# tester.net
KiCad netlist of a schematic drawn in EAGLE
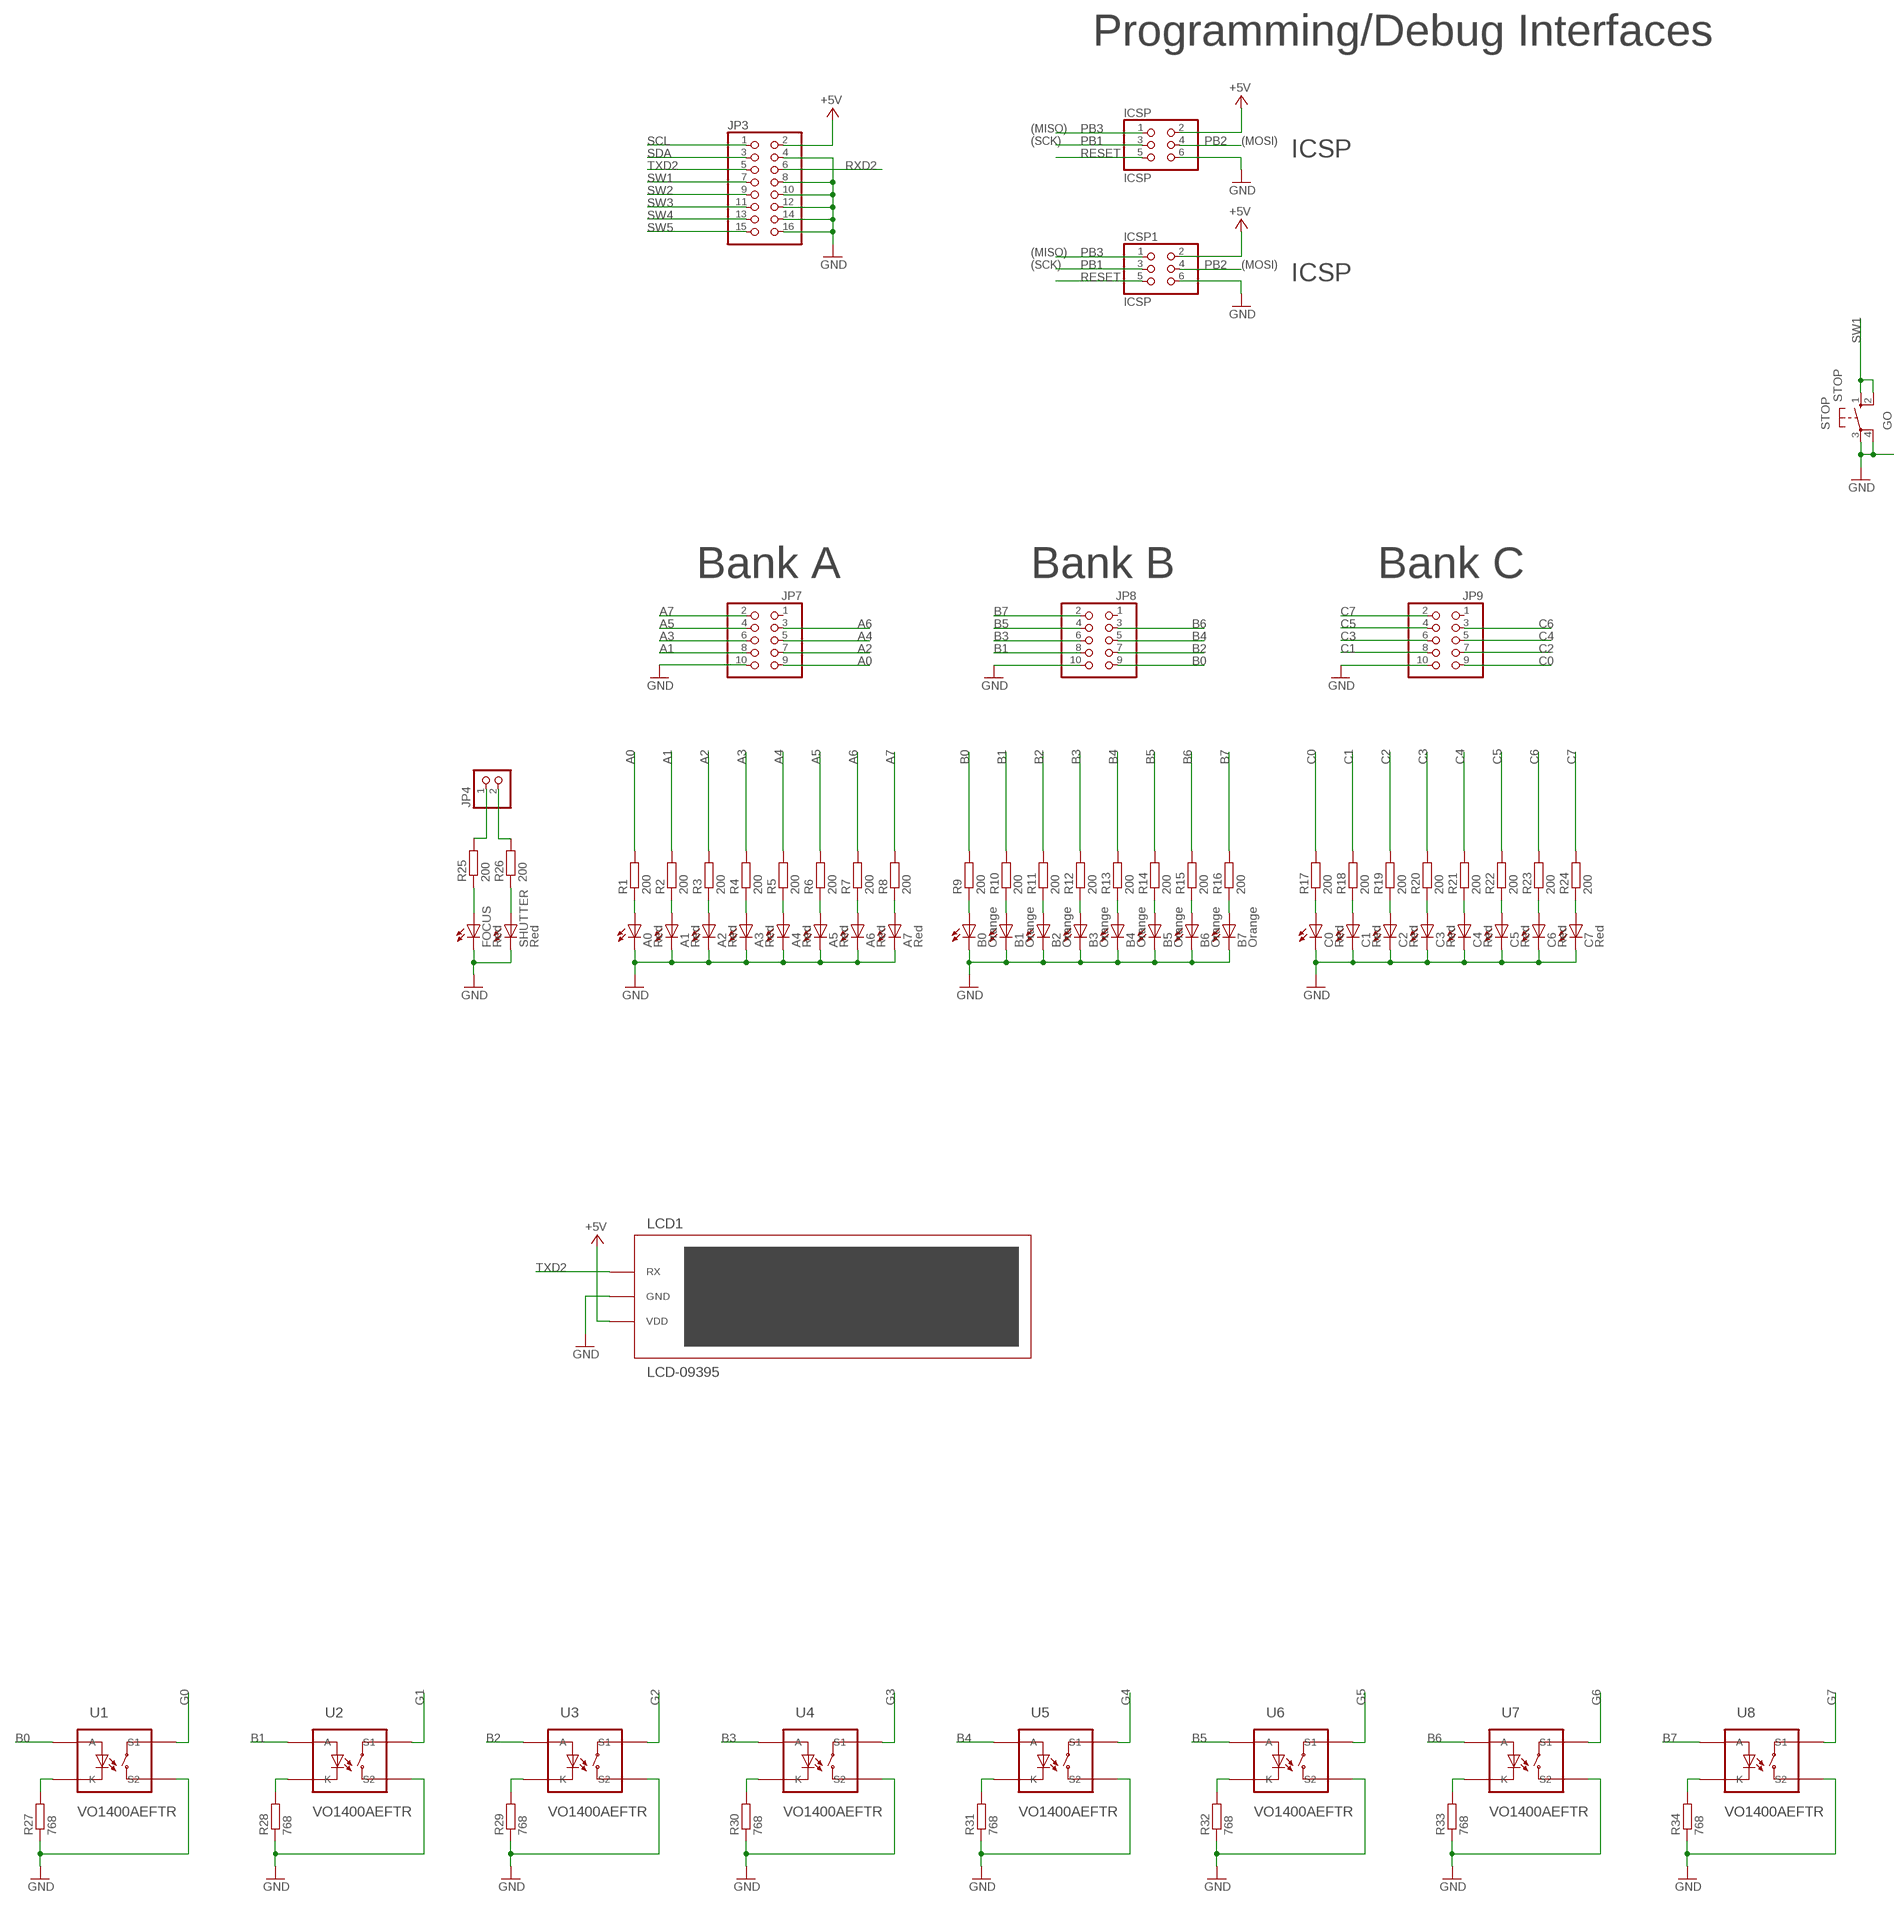
[diagram p0: schematic, sheet 1, part 1 of 2]
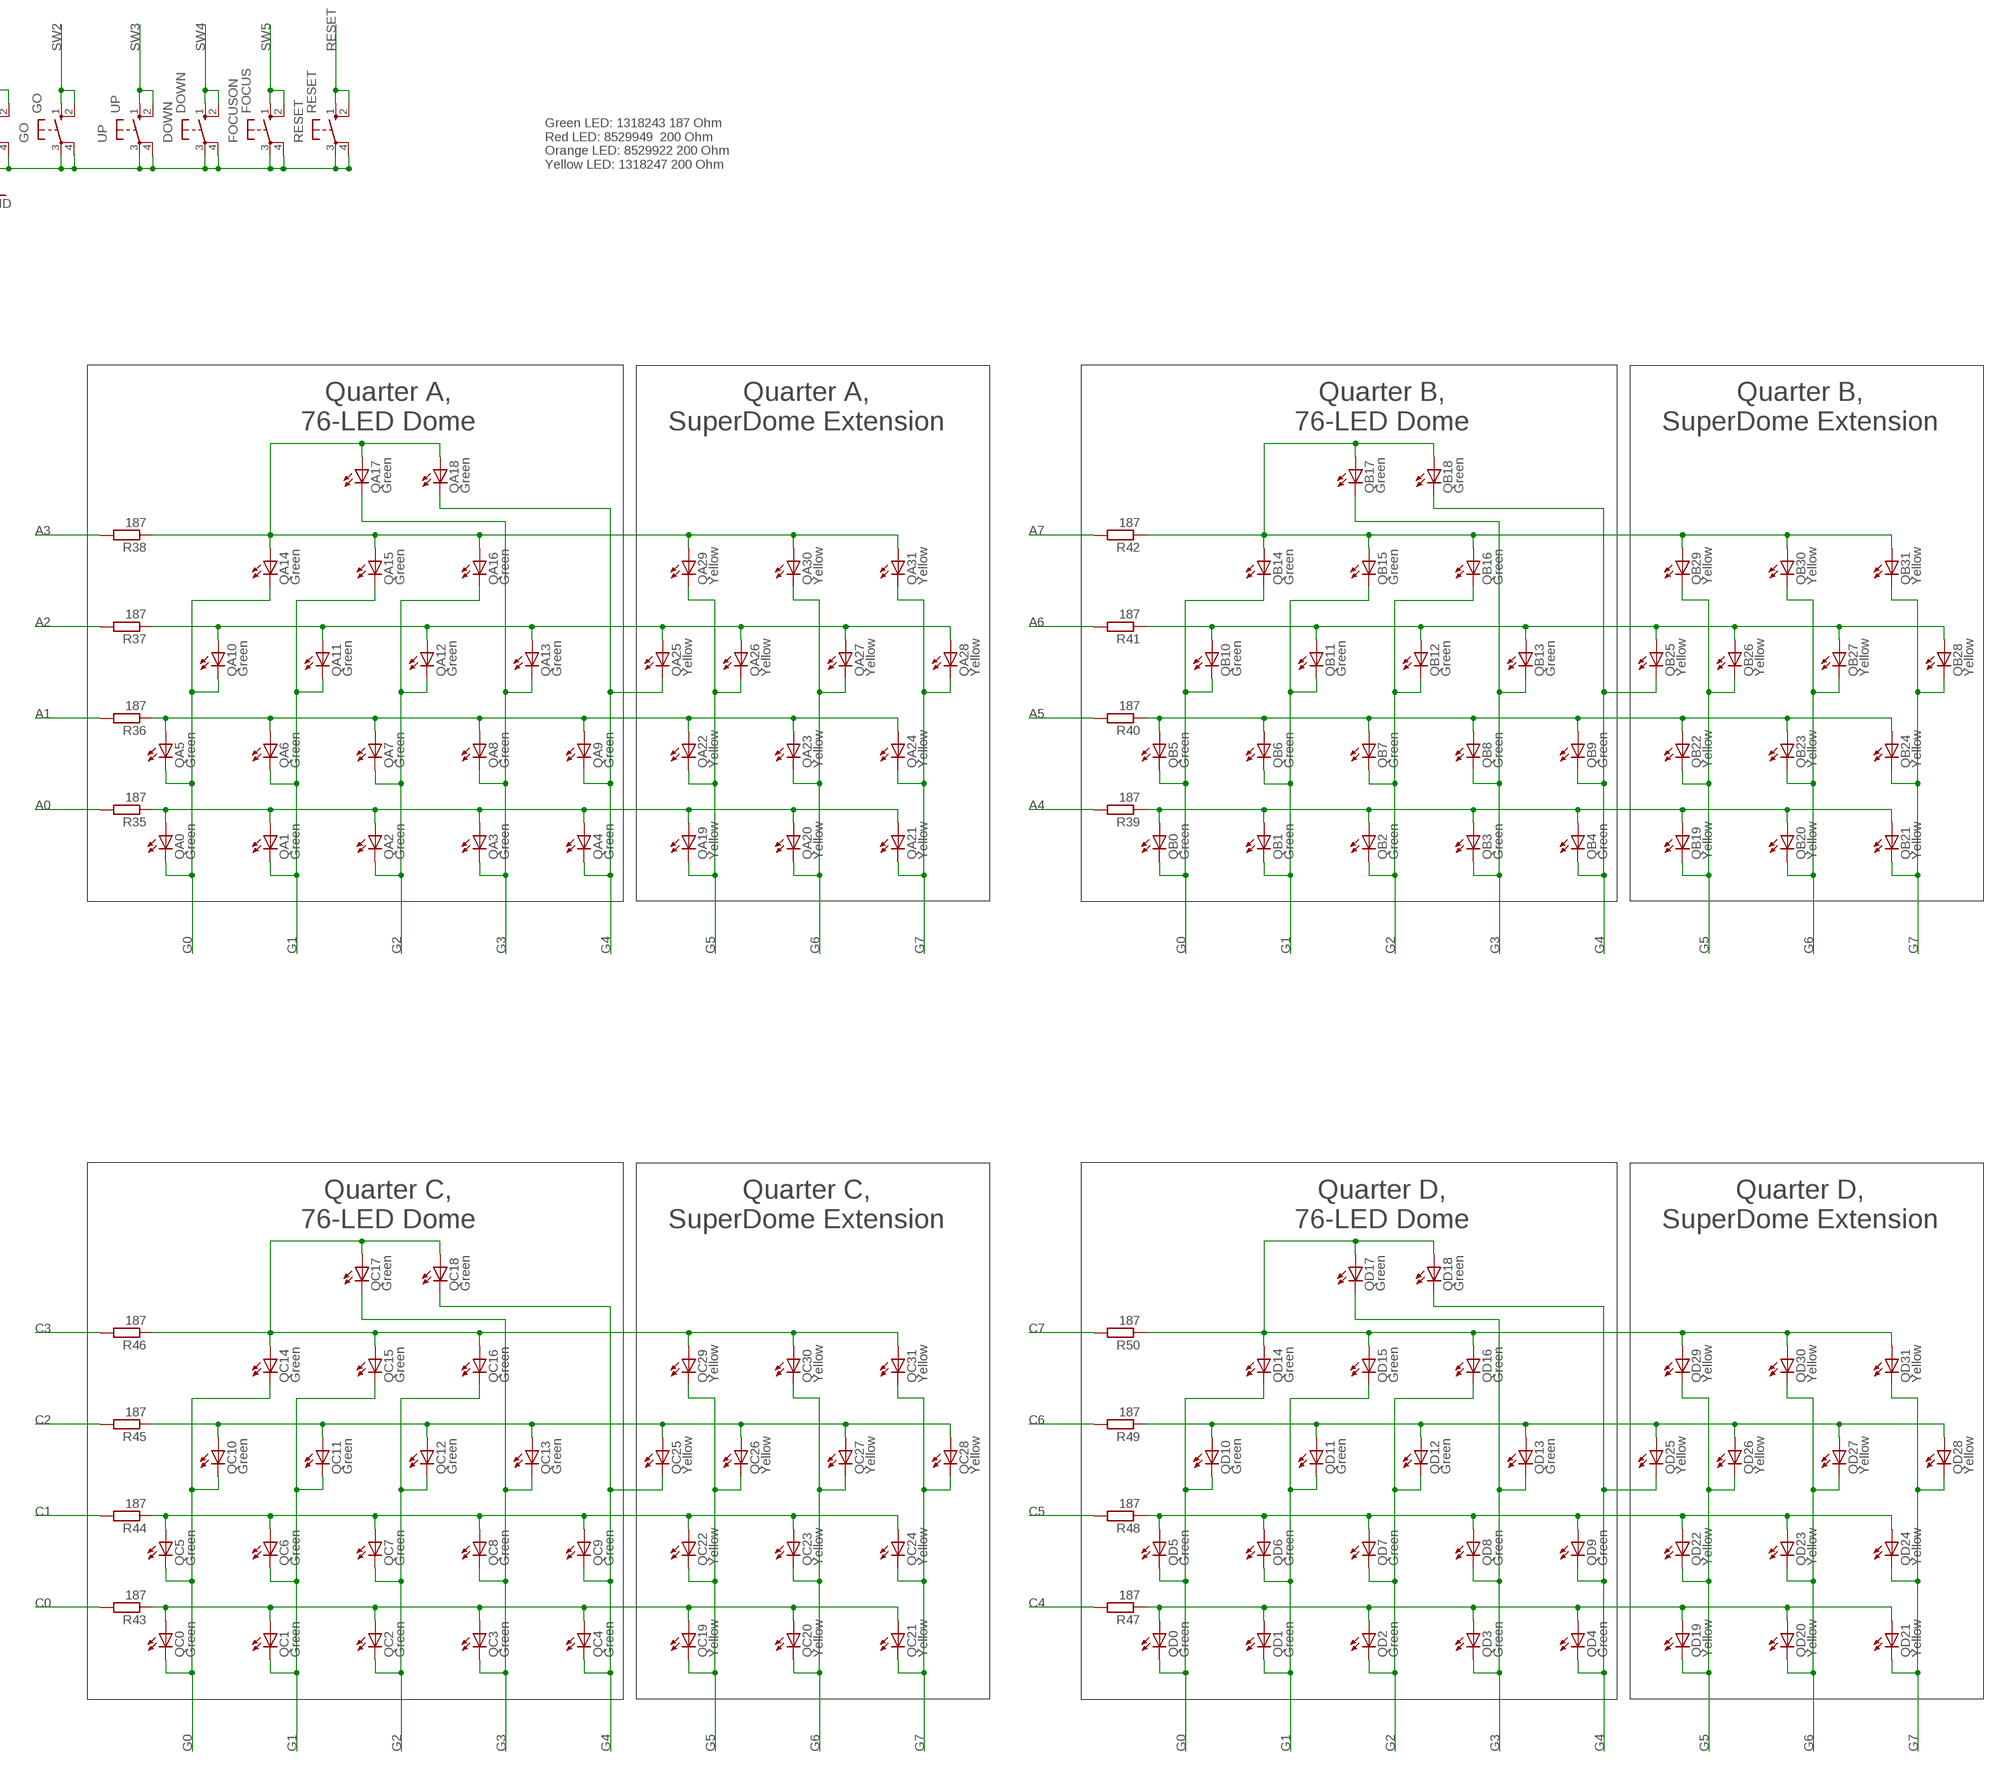
[diagram p1: schematic, sheet 1, part 2 of 2]

(export (version "E")
  (design (tool "Eeschema 10.0.6"))
  (components
    (comp (ref "A0")
      (value "Red")
      (footprint "eagle-import:CHIP-LED0805")
      (libsource (lib "eagle-import") (part "LEDCHIP-LED0805"))
    )
    (comp (ref "A1")
      (value "Red")
      (footprint "eagle-import:CHIP-LED0805")
      (libsource (lib "eagle-import") (part "LEDCHIP-LED0805"))
    )
    (comp (ref "A2")
      (value "Red")
      (footprint "eagle-import:CHIP-LED0805")
      (libsource (lib "eagle-import") (part "LEDCHIP-LED0805"))
    )
    (comp (ref "A3")
      (value "Red")
      (footprint "eagle-import:CHIP-LED0805")
      (libsource (lib "eagle-import") (part "LEDCHIP-LED0805"))
    )
    (comp (ref "A4")
      (value "Red")
      (footprint "eagle-import:CHIP-LED0805")
      (libsource (lib "eagle-import") (part "LEDCHIP-LED0805"))
    )
    (comp (ref "A5")
      (value "Red")
      (footprint "eagle-import:CHIP-LED0805")
      (libsource (lib "eagle-import") (part "LEDCHIP-LED0805"))
    )
    (comp (ref "A6")
      (value "Red")
      (footprint "eagle-import:CHIP-LED0805")
      (libsource (lib "eagle-import") (part "LEDCHIP-LED0805"))
    )
    (comp (ref "A7")
      (value "Red")
      (footprint "eagle-import:CHIP-LED0805")
      (libsource (lib "eagle-import") (part "LEDCHIP-LED0805"))
    )
    (comp (ref "B0")
      (value "Orange")
      (footprint "eagle-import:CHIP-LED0805")
      (libsource (lib "eagle-import") (part "LEDCHIP-LED0805"))
    )
    (comp (ref "B1")
      (value "Orange")
      (footprint "eagle-import:CHIP-LED0805")
      (libsource (lib "eagle-import") (part "LEDCHIP-LED0805"))
    )
    (comp (ref "B2")
      (value "Orange")
      (footprint "eagle-import:CHIP-LED0805")
      (libsource (lib "eagle-import") (part "LEDCHIP-LED0805"))
    )
    (comp (ref "B3")
      (value "Orange")
      (footprint "eagle-import:CHIP-LED0805")
      (libsource (lib "eagle-import") (part "LEDCHIP-LED0805"))
    )
    (comp (ref "B4")
      (value "Orange")
      (footprint "eagle-import:CHIP-LED0805")
      (libsource (lib "eagle-import") (part "LEDCHIP-LED0805"))
    )
    (comp (ref "B5")
      (value "Orange")
      (footprint "eagle-import:CHIP-LED0805")
      (libsource (lib "eagle-import") (part "LEDCHIP-LED0805"))
    )
    (comp (ref "B6")
      (value "Orange")
      (footprint "eagle-import:CHIP-LED0805")
      (libsource (lib "eagle-import") (part "LEDCHIP-LED0805"))
    )
    (comp (ref "B7")
      (value "Orange")
      (footprint "eagle-import:CHIP-LED0805")
      (libsource (lib "eagle-import") (part "LEDCHIP-LED0805"))
    )
    (comp (ref "C0")
      (value "Red")
      (footprint "eagle-import:CHIP-LED0805")
      (libsource (lib "eagle-import") (part "LEDCHIP-LED0805"))
    )
    (comp (ref "C1")
      (value "Red")
      (footprint "eagle-import:CHIP-LED0805")
      (libsource (lib "eagle-import") (part "LEDCHIP-LED0805"))
    )
    (comp (ref "C2")
      (value "Red")
      (footprint "eagle-import:CHIP-LED0805")
      (libsource (lib "eagle-import") (part "LEDCHIP-LED0805"))
    )
    (comp (ref "C3")
      (value "Red")
      (footprint "eagle-import:CHIP-LED0805")
      (libsource (lib "eagle-import") (part "LEDCHIP-LED0805"))
    )
    (comp (ref "C4")
      (value "Red")
      (footprint "eagle-import:CHIP-LED0805")
      (libsource (lib "eagle-import") (part "LEDCHIP-LED0805"))
    )
    (comp (ref "C5")
      (value "Red")
      (footprint "eagle-import:CHIP-LED0805")
      (libsource (lib "eagle-import") (part "LEDCHIP-LED0805"))
    )
    (comp (ref "C6")
      (value "Red")
      (footprint "eagle-import:CHIP-LED0805")
      (libsource (lib "eagle-import") (part "LEDCHIP-LED0805"))
    )
    (comp (ref "C7")
      (value "Red")
      (footprint "eagle-import:CHIP-LED0805")
      (libsource (lib "eagle-import") (part "LEDCHIP-LED0805"))
    )
    (comp (ref "DOWN")
      (value "DOWN")
      (footprint "eagle-import:B3F-10XX")
      (fields (field (name "MPN") "B3F-1000"))
      (libsource (lib "eagle-import") (part "10-XX"))
    )
    (comp (ref "FOCUS")
      (value "Red")
      (footprint "eagle-import:CHIP-LED0805")
      (libsource (lib "eagle-import") (part "LEDCHIP-LED0805"))
    )
    (comp (ref "FOCUSON")
      (value "FOCUS")
      (footprint "eagle-import:B3F-10XX")
      (fields (field (name "MPN") "B3F-1000"))
      (libsource (lib "eagle-import") (part "10-XX"))
    )
    (comp (ref "GO")
      (value "GO")
      (footprint "eagle-import:B3F-10XX")
      (fields (field (name "MPN") "B3F-1000"))
      (libsource (lib "eagle-import") (part "10-XX"))
    )
    (comp (ref "ICSP")
      (value "ICSP")
      (footprint "eagle-import:2X03")
      (libsource (lib "eagle-import") (part "PINHD-2X3"))
    )
    (comp (ref "ICSP1")
      (value "ICSP")
      (footprint "eagle-import:2X03")
      (libsource (lib "eagle-import") (part "PINHD-2X3"))
    )
    (comp (ref "JP3")
      (value "PINHD-2X8")
      (footprint "eagle-import:2X08")
      (libsource (lib "eagle-import") (part "PINHD-2X8"))
    )
    (comp (ref "JP4")
      (value "PINHD-1X2")
      (footprint "eagle-import:1X02")
      (libsource (lib "eagle-import") (part "PINHD-1X2"))
    )
    (comp (ref "JP7")
      (value "PINHD-2X5")
      (footprint "eagle-import:2X05")
      (libsource (lib "eagle-import") (part "PINHD-2X5"))
    )
    (comp (ref "JP8")
      (value "PINHD-2X5")
      (footprint "eagle-import:2X05")
      (libsource (lib "eagle-import") (part "PINHD-2X5"))
    )
    (comp (ref "JP9")
      (value "PINHD-2X5")
      (footprint "eagle-import:2X05")
      (libsource (lib "eagle-import") (part "PINHD-2X5"))
    )
    (comp (ref "LCD1")
      (value "LCD-09395")
      (footprint "eagle-import:LCD-09395")
      (libsource (lib "eagle-import") (part "LCD-09395"))
    )
    (comp (ref "QA0")
      (value "Green")
      (footprint "eagle-import:CHIP-LED0805")
      (libsource (lib "eagle-import") (part "LEDCHIP-LED0805"))
    )
    (comp (ref "QA1")
      (value "Green")
      (footprint "eagle-import:CHIP-LED0805")
      (libsource (lib "eagle-import") (part "LEDCHIP-LED0805"))
    )
    (comp (ref "QA2")
      (value "Green")
      (footprint "eagle-import:CHIP-LED0805")
      (libsource (lib "eagle-import") (part "LEDCHIP-LED0805"))
    )
    (comp (ref "QA3")
      (value "Green")
      (footprint "eagle-import:CHIP-LED0805")
      (libsource (lib "eagle-import") (part "LEDCHIP-LED0805"))
    )
    (comp (ref "QA4")
      (value "Green")
      (footprint "eagle-import:CHIP-LED0805")
      (libsource (lib "eagle-import") (part "LEDCHIP-LED0805"))
    )
    (comp (ref "QA5")
      (value "Green")
      (footprint "eagle-import:CHIP-LED0805")
      (libsource (lib "eagle-import") (part "LEDCHIP-LED0805"))
    )
    (comp (ref "QA6")
      (value "Green")
      (footprint "eagle-import:CHIP-LED0805")
      (libsource (lib "eagle-import") (part "LEDCHIP-LED0805"))
    )
    (comp (ref "QA7")
      (value "Green")
      (footprint "eagle-import:CHIP-LED0805")
      (libsource (lib "eagle-import") (part "LEDCHIP-LED0805"))
    )
    (comp (ref "QA8")
      (value "Green")
      (footprint "eagle-import:CHIP-LED0805")
      (libsource (lib "eagle-import") (part "LEDCHIP-LED0805"))
    )
    (comp (ref "QA9")
      (value "Green")
      (footprint "eagle-import:CHIP-LED0805")
      (libsource (lib "eagle-import") (part "LEDCHIP-LED0805"))
    )
    (comp (ref "QA10")
      (value "Green")
      (footprint "eagle-import:CHIP-LED0805")
      (libsource (lib "eagle-import") (part "LEDCHIP-LED0805"))
    )
    (comp (ref "QA11")
      (value "Green")
      (footprint "eagle-import:CHIP-LED0805")
      (libsource (lib "eagle-import") (part "LEDCHIP-LED0805"))
    )
    (comp (ref "QA12")
      (value "Green")
      (footprint "eagle-import:CHIP-LED0805")
      (libsource (lib "eagle-import") (part "LEDCHIP-LED0805"))
    )
    (comp (ref "QA13")
      (value "Green")
      (footprint "eagle-import:CHIP-LED0805")
      (libsource (lib "eagle-import") (part "LEDCHIP-LED0805"))
    )
    (comp (ref "QA14")
      (value "Green")
      (footprint "eagle-import:CHIP-LED0805")
      (libsource (lib "eagle-import") (part "LEDCHIP-LED0805"))
    )
    (comp (ref "QA15")
      (value "Green")
      (footprint "eagle-import:CHIP-LED0805")
      (libsource (lib "eagle-import") (part "LEDCHIP-LED0805"))
    )
    (comp (ref "QA16")
      (value "Green")
      (footprint "eagle-import:CHIP-LED0805")
      (libsource (lib "eagle-import") (part "LEDCHIP-LED0805"))
    )
    (comp (ref "QA17")
      (value "Green")
      (footprint "eagle-import:CHIP-LED0805")
      (libsource (lib "eagle-import") (part "LEDCHIP-LED0805"))
    )
    (comp (ref "QA18")
      (value "Green")
      (footprint "eagle-import:CHIP-LED0805")
      (libsource (lib "eagle-import") (part "LEDCHIP-LED0805"))
    )
    (comp (ref "QA19")
      (value "Yellow")
      (footprint "eagle-import:CHIP-LED0805")
      (libsource (lib "eagle-import") (part "LEDCHIP-LED0805"))
    )
    (comp (ref "QA20")
      (value "Yellow")
      (footprint "eagle-import:CHIP-LED0805")
      (libsource (lib "eagle-import") (part "LEDCHIP-LED0805"))
    )
    (comp (ref "QA21")
      (value "Yellow")
      (footprint "eagle-import:CHIP-LED0805")
      (libsource (lib "eagle-import") (part "LEDCHIP-LED0805"))
    )
    (comp (ref "QA22")
      (value "Yellow")
      (footprint "eagle-import:CHIP-LED0805")
      (libsource (lib "eagle-import") (part "LEDCHIP-LED0805"))
    )
    (comp (ref "QA23")
      (value "Yellow")
      (footprint "eagle-import:CHIP-LED0805")
      (libsource (lib "eagle-import") (part "LEDCHIP-LED0805"))
    )
    (comp (ref "QA24")
      (value "Yellow")
      (footprint "eagle-import:CHIP-LED0805")
      (libsource (lib "eagle-import") (part "LEDCHIP-LED0805"))
    )
    (comp (ref "QA25")
      (value "Yellow")
      (footprint "eagle-import:CHIP-LED0805")
      (libsource (lib "eagle-import") (part "LEDCHIP-LED0805"))
    )
    (comp (ref "QA26")
      (value "Yellow")
      (footprint "eagle-import:CHIP-LED0805")
      (libsource (lib "eagle-import") (part "LEDCHIP-LED0805"))
    )
    (comp (ref "QA27")
      (value "Yellow")
      (footprint "eagle-import:CHIP-LED0805")
      (libsource (lib "eagle-import") (part "LEDCHIP-LED0805"))
    )
    (comp (ref "QA28")
      (value "Yellow")
      (footprint "eagle-import:CHIP-LED0805")
      (libsource (lib "eagle-import") (part "LEDCHIP-LED0805"))
    )
    (comp (ref "QA29")
      (value "Yellow")
      (footprint "eagle-import:CHIP-LED0805")
      (libsource (lib "eagle-import") (part "LEDCHIP-LED0805"))
    )
    (comp (ref "QA30")
      (value "Yellow")
      (footprint "eagle-import:CHIP-LED0805")
      (libsource (lib "eagle-import") (part "LEDCHIP-LED0805"))
    )
    (comp (ref "QA31")
      (value "Yellow")
      (footprint "eagle-import:CHIP-LED0805")
      (libsource (lib "eagle-import") (part "LEDCHIP-LED0805"))
    )
    (comp (ref "QB0")
      (value "Green")
      (footprint "eagle-import:CHIP-LED0805")
      (libsource (lib "eagle-import") (part "LEDCHIP-LED0805"))
    )
    (comp (ref "QB1")
      (value "Green")
      (footprint "eagle-import:CHIP-LED0805")
      (libsource (lib "eagle-import") (part "LEDCHIP-LED0805"))
    )
    (comp (ref "QB2")
      (value "Green")
      (footprint "eagle-import:CHIP-LED0805")
      (libsource (lib "eagle-import") (part "LEDCHIP-LED0805"))
    )
    (comp (ref "QB3")
      (value "Green")
      (footprint "eagle-import:CHIP-LED0805")
      (libsource (lib "eagle-import") (part "LEDCHIP-LED0805"))
    )
    (comp (ref "QB4")
      (value "Green")
      (footprint "eagle-import:CHIP-LED0805")
      (libsource (lib "eagle-import") (part "LEDCHIP-LED0805"))
    )
    (comp (ref "QB5")
      (value "Green")
      (footprint "eagle-import:CHIP-LED0805")
      (libsource (lib "eagle-import") (part "LEDCHIP-LED0805"))
    )
    (comp (ref "QB6")
      (value "Green")
      (footprint "eagle-import:CHIP-LED0805")
      (libsource (lib "eagle-import") (part "LEDCHIP-LED0805"))
    )
    (comp (ref "QB7")
      (value "Green")
      (footprint "eagle-import:CHIP-LED0805")
      (libsource (lib "eagle-import") (part "LEDCHIP-LED0805"))
    )
    (comp (ref "QB8")
      (value "Green")
      (footprint "eagle-import:CHIP-LED0805")
      (libsource (lib "eagle-import") (part "LEDCHIP-LED0805"))
    )
    (comp (ref "QB9")
      (value "Green")
      (footprint "eagle-import:CHIP-LED0805")
      (libsource (lib "eagle-import") (part "LEDCHIP-LED0805"))
    )
    (comp (ref "QB10")
      (value "Green")
      (footprint "eagle-import:CHIP-LED0805")
      (libsource (lib "eagle-import") (part "LEDCHIP-LED0805"))
    )
    (comp (ref "QB11")
      (value "Green")
      (footprint "eagle-import:CHIP-LED0805")
      (libsource (lib "eagle-import") (part "LEDCHIP-LED0805"))
    )
    (comp (ref "QB12")
      (value "Green")
      (footprint "eagle-import:CHIP-LED0805")
      (libsource (lib "eagle-import") (part "LEDCHIP-LED0805"))
    )
    (comp (ref "QB13")
      (value "Green")
      (footprint "eagle-import:CHIP-LED0805")
      (libsource (lib "eagle-import") (part "LEDCHIP-LED0805"))
    )
    (comp (ref "QB14")
      (value "Green")
      (footprint "eagle-import:CHIP-LED0805")
      (libsource (lib "eagle-import") (part "LEDCHIP-LED0805"))
    )
    (comp (ref "QB15")
      (value "Green")
      (footprint "eagle-import:CHIP-LED0805")
      (libsource (lib "eagle-import") (part "LEDCHIP-LED0805"))
    )
    (comp (ref "QB16")
      (value "Green")
      (footprint "eagle-import:CHIP-LED0805")
      (libsource (lib "eagle-import") (part "LEDCHIP-LED0805"))
    )
    (comp (ref "QB17")
      (value "Green")
      (footprint "eagle-import:CHIP-LED0805")
      (libsource (lib "eagle-import") (part "LEDCHIP-LED0805"))
    )
    (comp (ref "QB18")
      (value "Green")
      (footprint "eagle-import:CHIP-LED0805")
      (libsource (lib "eagle-import") (part "LEDCHIP-LED0805"))
    )
    (comp (ref "QB19")
      (value "Yellow")
      (footprint "eagle-import:CHIP-LED0805")
      (libsource (lib "eagle-import") (part "LEDCHIP-LED0805"))
    )
    (comp (ref "QB20")
      (value "Yellow")
      (footprint "eagle-import:CHIP-LED0805")
      (libsource (lib "eagle-import") (part "LEDCHIP-LED0805"))
    )
    (comp (ref "QB21")
      (value "Yellow")
      (footprint "eagle-import:CHIP-LED0805")
      (libsource (lib "eagle-import") (part "LEDCHIP-LED0805"))
    )
    (comp (ref "QB22")
      (value "Yellow")
      (footprint "eagle-import:CHIP-LED0805")
      (libsource (lib "eagle-import") (part "LEDCHIP-LED0805"))
    )
    (comp (ref "QB23")
      (value "Yellow")
      (footprint "eagle-import:CHIP-LED0805")
      (libsource (lib "eagle-import") (part "LEDCHIP-LED0805"))
    )
    (comp (ref "QB24")
      (value "Yellow")
      (footprint "eagle-import:CHIP-LED0805")
      (libsource (lib "eagle-import") (part "LEDCHIP-LED0805"))
    )
    (comp (ref "QB25")
      (value "Yellow")
      (footprint "eagle-import:CHIP-LED0805")
      (libsource (lib "eagle-import") (part "LEDCHIP-LED0805"))
    )
    (comp (ref "QB26")
      (value "Yellow")
      (footprint "eagle-import:CHIP-LED0805")
      (libsource (lib "eagle-import") (part "LEDCHIP-LED0805"))
    )
    (comp (ref "QB27")
      (value "Yellow")
      (footprint "eagle-import:CHIP-LED0805")
      (libsource (lib "eagle-import") (part "LEDCHIP-LED0805"))
    )
    (comp (ref "QB28")
      (value "Yellow")
      (footprint "eagle-import:CHIP-LED0805")
      (libsource (lib "eagle-import") (part "LEDCHIP-LED0805"))
    )
    (comp (ref "QB29")
      (value "Yellow")
      (footprint "eagle-import:CHIP-LED0805")
      (libsource (lib "eagle-import") (part "LEDCHIP-LED0805"))
    )
    (comp (ref "QB30")
      (value "Yellow")
      (footprint "eagle-import:CHIP-LED0805")
      (libsource (lib "eagle-import") (part "LEDCHIP-LED0805"))
    )
    (comp (ref "QB31")
      (value "Yellow")
      (footprint "eagle-import:CHIP-LED0805")
      (libsource (lib "eagle-import") (part "LEDCHIP-LED0805"))
    )
    (comp (ref "QC0")
      (value "Green")
      (footprint "eagle-import:CHIP-LED0805")
      (libsource (lib "eagle-import") (part "LEDCHIP-LED0805"))
    )
    (comp (ref "QC1")
      (value "Green")
      (footprint "eagle-import:CHIP-LED0805")
      (libsource (lib "eagle-import") (part "LEDCHIP-LED0805"))
    )
    (comp (ref "QC2")
      (value "Green")
      (footprint "eagle-import:CHIP-LED0805")
      (libsource (lib "eagle-import") (part "LEDCHIP-LED0805"))
    )
    (comp (ref "QC3")
      (value "Green")
      (footprint "eagle-import:CHIP-LED0805")
      (libsource (lib "eagle-import") (part "LEDCHIP-LED0805"))
    )
    (comp (ref "QC4")
      (value "Green")
      (footprint "eagle-import:CHIP-LED0805")
      (libsource (lib "eagle-import") (part "LEDCHIP-LED0805"))
    )
    (comp (ref "QC5")
      (value "Green")
      (footprint "eagle-import:CHIP-LED0805")
      (libsource (lib "eagle-import") (part "LEDCHIP-LED0805"))
    )
    (comp (ref "QC6")
      (value "Green")
      (footprint "eagle-import:CHIP-LED0805")
      (libsource (lib "eagle-import") (part "LEDCHIP-LED0805"))
    )
    (comp (ref "QC7")
      (value "Green")
      (footprint "eagle-import:CHIP-LED0805")
      (libsource (lib "eagle-import") (part "LEDCHIP-LED0805"))
    )
    (comp (ref "QC8")
      (value "Green")
      (footprint "eagle-import:CHIP-LED0805")
      (libsource (lib "eagle-import") (part "LEDCHIP-LED0805"))
    )
    (comp (ref "QC9")
      (value "Green")
      (footprint "eagle-import:CHIP-LED0805")
      (libsource (lib "eagle-import") (part "LEDCHIP-LED0805"))
    )
    (comp (ref "QC10")
      (value "Green")
      (footprint "eagle-import:CHIP-LED0805")
      (libsource (lib "eagle-import") (part "LEDCHIP-LED0805"))
    )
    (comp (ref "QC11")
      (value "Green")
      (footprint "eagle-import:CHIP-LED0805")
      (libsource (lib "eagle-import") (part "LEDCHIP-LED0805"))
    )
    (comp (ref "QC12")
      (value "Green")
      (footprint "eagle-import:CHIP-LED0805")
      (libsource (lib "eagle-import") (part "LEDCHIP-LED0805"))
    )
    (comp (ref "QC13")
      (value "Green")
      (footprint "eagle-import:CHIP-LED0805")
      (libsource (lib "eagle-import") (part "LEDCHIP-LED0805"))
    )
    (comp (ref "QC14")
      (value "Green")
      (footprint "eagle-import:CHIP-LED0805")
      (libsource (lib "eagle-import") (part "LEDCHIP-LED0805"))
    )
    (comp (ref "QC15")
      (value "Green")
      (footprint "eagle-import:CHIP-LED0805")
      (libsource (lib "eagle-import") (part "LEDCHIP-LED0805"))
    )
    (comp (ref "QC16")
      (value "Green")
      (footprint "eagle-import:CHIP-LED0805")
      (libsource (lib "eagle-import") (part "LEDCHIP-LED0805"))
    )
    (comp (ref "QC17")
      (value "Green")
      (footprint "eagle-import:CHIP-LED0805")
      (libsource (lib "eagle-import") (part "LEDCHIP-LED0805"))
    )
    (comp (ref "QC18")
      (value "Green")
      (footprint "eagle-import:CHIP-LED0805")
      (libsource (lib "eagle-import") (part "LEDCHIP-LED0805"))
    )
    (comp (ref "QC19")
      (value "Yellow")
      (footprint "eagle-import:CHIP-LED0805")
      (libsource (lib "eagle-import") (part "LEDCHIP-LED0805"))
    )
    (comp (ref "QC20")
      (value "Yellow")
      (footprint "eagle-import:CHIP-LED0805")
      (libsource (lib "eagle-import") (part "LEDCHIP-LED0805"))
    )
    (comp (ref "QC21")
      (value "Yellow")
      (footprint "eagle-import:CHIP-LED0805")
      (libsource (lib "eagle-import") (part "LEDCHIP-LED0805"))
    )
    (comp (ref "QC22")
      (value "Yellow")
      (footprint "eagle-import:CHIP-LED0805")
      (libsource (lib "eagle-import") (part "LEDCHIP-LED0805"))
    )
    (comp (ref "QC23")
      (value "Yellow")
      (footprint "eagle-import:CHIP-LED0805")
      (libsource (lib "eagle-import") (part "LEDCHIP-LED0805"))
    )
    (comp (ref "QC24")
      (value "Yellow")
      (footprint "eagle-import:CHIP-LED0805")
      (libsource (lib "eagle-import") (part "LEDCHIP-LED0805"))
    )
    (comp (ref "QC25")
      (value "Yellow")
      (footprint "eagle-import:CHIP-LED0805")
      (libsource (lib "eagle-import") (part "LEDCHIP-LED0805"))
    )
    (comp (ref "QC26")
      (value "Yellow")
      (footprint "eagle-import:CHIP-LED0805")
      (libsource (lib "eagle-import") (part "LEDCHIP-LED0805"))
    )
    (comp (ref "QC27")
      (value "Yellow")
      (footprint "eagle-import:CHIP-LED0805")
      (libsource (lib "eagle-import") (part "LEDCHIP-LED0805"))
    )
    (comp (ref "QC28")
      (value "Yellow")
      (footprint "eagle-import:CHIP-LED0805")
      (libsource (lib "eagle-import") (part "LEDCHIP-LED0805"))
    )
    (comp (ref "QC29")
      (value "Yellow")
      (footprint "eagle-import:CHIP-LED0805")
      (libsource (lib "eagle-import") (part "LEDCHIP-LED0805"))
    )
    (comp (ref "QC30")
      (value "Yellow")
      (footprint "eagle-import:CHIP-LED0805")
      (libsource (lib "eagle-import") (part "LEDCHIP-LED0805"))
    )
    (comp (ref "QC31")
      (value "Yellow")
      (footprint "eagle-import:CHIP-LED0805")
      (libsource (lib "eagle-import") (part "LEDCHIP-LED0805"))
    )
    (comp (ref "QD0")
      (value "Green")
      (footprint "eagle-import:CHIP-LED0805")
      (libsource (lib "eagle-import") (part "LEDCHIP-LED0805"))
    )
    (comp (ref "QD1")
      (value "Green")
      (footprint "eagle-import:CHIP-LED0805")
      (libsource (lib "eagle-import") (part "LEDCHIP-LED0805"))
    )
    (comp (ref "QD2")
      (value "Green")
      (footprint "eagle-import:CHIP-LED0805")
      (libsource (lib "eagle-import") (part "LEDCHIP-LED0805"))
    )
    (comp (ref "QD3")
      (value "Green")
      (footprint "eagle-import:CHIP-LED0805")
      (libsource (lib "eagle-import") (part "LEDCHIP-LED0805"))
    )
    (comp (ref "QD4")
      (value "Green")
      (footprint "eagle-import:CHIP-LED0805")
      (libsource (lib "eagle-import") (part "LEDCHIP-LED0805"))
    )
    (comp (ref "QD5")
      (value "Green")
      (footprint "eagle-import:CHIP-LED0805")
      (libsource (lib "eagle-import") (part "LEDCHIP-LED0805"))
    )
    (comp (ref "QD6")
      (value "Green")
      (footprint "eagle-import:CHIP-LED0805")
      (libsource (lib "eagle-import") (part "LEDCHIP-LED0805"))
    )
    (comp (ref "QD7")
      (value "Green")
      (footprint "eagle-import:CHIP-LED0805")
      (libsource (lib "eagle-import") (part "LEDCHIP-LED0805"))
    )
    (comp (ref "QD8")
      (value "Green")
      (footprint "eagle-import:CHIP-LED0805")
      (libsource (lib "eagle-import") (part "LEDCHIP-LED0805"))
    )
    (comp (ref "QD9")
      (value "Green")
      (footprint "eagle-import:CHIP-LED0805")
      (libsource (lib "eagle-import") (part "LEDCHIP-LED0805"))
    )
    (comp (ref "QD10")
      (value "Green")
      (footprint "eagle-import:CHIP-LED0805")
      (libsource (lib "eagle-import") (part "LEDCHIP-LED0805"))
    )
    (comp (ref "QD11")
      (value "Green")
      (footprint "eagle-import:CHIP-LED0805")
      (libsource (lib "eagle-import") (part "LEDCHIP-LED0805"))
    )
    (comp (ref "QD12")
      (value "Green")
      (footprint "eagle-import:CHIP-LED0805")
      (libsource (lib "eagle-import") (part "LEDCHIP-LED0805"))
    )
    (comp (ref "QD13")
      (value "Green")
      (footprint "eagle-import:CHIP-LED0805")
      (libsource (lib "eagle-import") (part "LEDCHIP-LED0805"))
    )
    (comp (ref "QD14")
      (value "Green")
      (footprint "eagle-import:CHIP-LED0805")
      (libsource (lib "eagle-import") (part "LEDCHIP-LED0805"))
    )
    (comp (ref "QD15")
      (value "Green")
      (footprint "eagle-import:CHIP-LED0805")
      (libsource (lib "eagle-import") (part "LEDCHIP-LED0805"))
    )
    (comp (ref "QD16")
      (value "Green")
      (footprint "eagle-import:CHIP-LED0805")
      (libsource (lib "eagle-import") (part "LEDCHIP-LED0805"))
    )
    (comp (ref "QD17")
      (value "Green")
      (footprint "eagle-import:CHIP-LED0805")
      (libsource (lib "eagle-import") (part "LEDCHIP-LED0805"))
    )
    (comp (ref "QD18")
      (value "Green")
      (footprint "eagle-import:CHIP-LED0805")
      (libsource (lib "eagle-import") (part "LEDCHIP-LED0805"))
    )
    (comp (ref "QD19")
      (value "Yellow")
      (footprint "eagle-import:CHIP-LED0805")
      (libsource (lib "eagle-import") (part "LEDCHIP-LED0805"))
    )
    (comp (ref "QD20")
      (value "Yellow")
      (footprint "eagle-import:CHIP-LED0805")
      (libsource (lib "eagle-import") (part "LEDCHIP-LED0805"))
    )
    (comp (ref "QD21")
      (value "Yellow")
      (footprint "eagle-import:CHIP-LED0805")
      (libsource (lib "eagle-import") (part "LEDCHIP-LED0805"))
    )
    (comp (ref "QD22")
      (value "Yellow")
      (footprint "eagle-import:CHIP-LED0805")
      (libsource (lib "eagle-import") (part "LEDCHIP-LED0805"))
    )
    (comp (ref "QD23")
      (value "Yellow")
      (footprint "eagle-import:CHIP-LED0805")
      (libsource (lib "eagle-import") (part "LEDCHIP-LED0805"))
    )
    (comp (ref "QD24")
      (value "Yellow")
      (footprint "eagle-import:CHIP-LED0805")
      (libsource (lib "eagle-import") (part "LEDCHIP-LED0805"))
    )
    (comp (ref "QD25")
      (value "Yellow")
      (footprint "eagle-import:CHIP-LED0805")
      (libsource (lib "eagle-import") (part "LEDCHIP-LED0805"))
    )
    (comp (ref "QD26")
      (value "Yellow")
      (footprint "eagle-import:CHIP-LED0805")
      (libsource (lib "eagle-import") (part "LEDCHIP-LED0805"))
    )
    (comp (ref "QD27")
      (value "Yellow")
      (footprint "eagle-import:CHIP-LED0805")
      (libsource (lib "eagle-import") (part "LEDCHIP-LED0805"))
    )
    (comp (ref "QD28")
      (value "Yellow")
      (footprint "eagle-import:CHIP-LED0805")
      (libsource (lib "eagle-import") (part "LEDCHIP-LED0805"))
    )
    (comp (ref "QD29")
      (value "Yellow")
      (footprint "eagle-import:CHIP-LED0805")
      (libsource (lib "eagle-import") (part "LEDCHIP-LED0805"))
    )
    (comp (ref "QD30")
      (value "Yellow")
      (footprint "eagle-import:CHIP-LED0805")
      (libsource (lib "eagle-import") (part "LEDCHIP-LED0805"))
    )
    (comp (ref "QD31")
      (value "Yellow")
      (footprint "eagle-import:CHIP-LED0805")
      (libsource (lib "eagle-import") (part "LEDCHIP-LED0805"))
    )
    (comp (ref "R1")
      (value "200")
      (footprint "eagle-import:R0805")
      (libsource (lib "eagle-import") (part "R-EU_R0805"))
    )
    (comp (ref "R2")
      (value "200")
      (footprint "eagle-import:R0805")
      (libsource (lib "eagle-import") (part "R-EU_R0805"))
    )
    (comp (ref "R3")
      (value "200")
      (footprint "eagle-import:R0805")
      (libsource (lib "eagle-import") (part "R-EU_R0805"))
    )
    (comp (ref "R4")
      (value "200")
      (footprint "eagle-import:R0805")
      (libsource (lib "eagle-import") (part "R-EU_R0805"))
    )
    (comp (ref "R5")
      (value "200")
      (footprint "eagle-import:R0805")
      (libsource (lib "eagle-import") (part "R-EU_R0805"))
    )
    (comp (ref "R6")
      (value "200")
      (footprint "eagle-import:R0805")
      (libsource (lib "eagle-import") (part "R-EU_R0805"))
    )
    (comp (ref "R7")
      (value "200")
      (footprint "eagle-import:R0805")
      (libsource (lib "eagle-import") (part "R-EU_R0805"))
    )
    (comp (ref "R8")
      (value "200")
      (footprint "eagle-import:R0805")
      (libsource (lib "eagle-import") (part "R-EU_R0805"))
    )
    (comp (ref "R9")
      (value "200")
      (footprint "eagle-import:R0805")
      (libsource (lib "eagle-import") (part "R-EU_R0805"))
    )
    (comp (ref "R10")
      (value "200")
      (footprint "eagle-import:R0805")
      (libsource (lib "eagle-import") (part "R-EU_R0805"))
    )
    (comp (ref "R11")
      (value "200")
      (footprint "eagle-import:R0805")
      (libsource (lib "eagle-import") (part "R-EU_R0805"))
    )
    (comp (ref "R12")
      (value "200")
      (footprint "eagle-import:R0805")
      (libsource (lib "eagle-import") (part "R-EU_R0805"))
    )
    (comp (ref "R13")
      (value "200")
      (footprint "eagle-import:R0805")
      (libsource (lib "eagle-import") (part "R-EU_R0805"))
    )
    (comp (ref "R14")
      (value "200")
      (footprint "eagle-import:R0805")
      (libsource (lib "eagle-import") (part "R-EU_R0805"))
    )
    (comp (ref "R15")
      (value "200")
      (footprint "eagle-import:R0805")
      (libsource (lib "eagle-import") (part "R-EU_R0805"))
    )
    (comp (ref "R16")
      (value "200")
      (footprint "eagle-import:R0805")
      (libsource (lib "eagle-import") (part "R-EU_R0805"))
    )
    (comp (ref "R17")
      (value "200")
      (footprint "eagle-import:R0805")
      (libsource (lib "eagle-import") (part "R-EU_R0805"))
    )
    (comp (ref "R18")
      (value "200")
      (footprint "eagle-import:R0805")
      (libsource (lib "eagle-import") (part "R-EU_R0805"))
    )
    (comp (ref "R19")
      (value "200")
      (footprint "eagle-import:R0805")
      (libsource (lib "eagle-import") (part "R-EU_R0805"))
    )
    (comp (ref "R20")
      (value "200")
      (footprint "eagle-import:R0805")
      (libsource (lib "eagle-import") (part "R-EU_R0805"))
    )
    (comp (ref "R21")
      (value "200")
      (footprint "eagle-import:R0805")
      (libsource (lib "eagle-import") (part "R-EU_R0805"))
    )
    (comp (ref "R22")
      (value "200")
      (footprint "eagle-import:R0805")
      (libsource (lib "eagle-import") (part "R-EU_R0805"))
    )
    (comp (ref "R23")
      (value "200")
      (footprint "eagle-import:R0805")
      (libsource (lib "eagle-import") (part "R-EU_R0805"))
    )
    (comp (ref "R24")
      (value "200")
      (footprint "eagle-import:R0805")
      (libsource (lib "eagle-import") (part "R-EU_R0805"))
    )
    (comp (ref "R25")
      (value "200")
      (footprint "eagle-import:R0805")
      (libsource (lib "eagle-import") (part "R-EU_R0805"))
    )
    (comp (ref "R26")
      (value "200")
      (footprint "eagle-import:R0805")
      (libsource (lib "eagle-import") (part "R-EU_R0805"))
    )
    (comp (ref "R27")
      (value "768")
      (footprint "eagle-import:R0805")
      (libsource (lib "eagle-import") (part "R-EU_R0805"))
    )
    (comp (ref "R28")
      (value "768")
      (footprint "eagle-import:R0805")
      (libsource (lib "eagle-import") (part "R-EU_R0805"))
    )
    (comp (ref "R29")
      (value "768")
      (footprint "eagle-import:R0805")
      (libsource (lib "eagle-import") (part "R-EU_R0805"))
    )
    (comp (ref "R30")
      (value "768")
      (footprint "eagle-import:R0805")
      (libsource (lib "eagle-import") (part "R-EU_R0805"))
    )
    (comp (ref "R31")
      (value "768")
      (footprint "eagle-import:R0805")
      (libsource (lib "eagle-import") (part "R-EU_R0805"))
    )
    (comp (ref "R32")
      (value "768")
      (footprint "eagle-import:R0805")
      (libsource (lib "eagle-import") (part "R-EU_R0805"))
    )
    (comp (ref "R33")
      (value "768")
      (footprint "eagle-import:R0805")
      (libsource (lib "eagle-import") (part "R-EU_R0805"))
    )
    (comp (ref "R34")
      (value "768")
      (footprint "eagle-import:R0805")
      (libsource (lib "eagle-import") (part "R-EU_R0805"))
    )
    (comp (ref "R35")
      (value "187")
      (footprint "eagle-import:R0805")
      (libsource (lib "eagle-import") (part "R-EU_R0805"))
    )
    (comp (ref "R36")
      (value "187")
      (footprint "eagle-import:R0805")
      (libsource (lib "eagle-import") (part "R-EU_R0805"))
    )
    (comp (ref "R37")
      (value "187")
      (footprint "eagle-import:R0805")
      (libsource (lib "eagle-import") (part "R-EU_R0805"))
    )
    (comp (ref "R38")
      (value "187")
      (footprint "eagle-import:R0805")
      (libsource (lib "eagle-import") (part "R-EU_R0805"))
    )
    (comp (ref "R39")
      (value "187")
      (footprint "eagle-import:R0805")
      (libsource (lib "eagle-import") (part "R-EU_R0805"))
    )
    (comp (ref "R40")
      (value "187")
      (footprint "eagle-import:R0805")
      (libsource (lib "eagle-import") (part "R-EU_R0805"))
    )
    (comp (ref "R41")
      (value "187")
      (footprint "eagle-import:R0805")
      (libsource (lib "eagle-import") (part "R-EU_R0805"))
    )
    (comp (ref "R42")
      (value "187")
      (footprint "eagle-import:R0805")
      (libsource (lib "eagle-import") (part "R-EU_R0805"))
    )
    (comp (ref "R43")
      (value "187")
      (footprint "eagle-import:R0805")
      (libsource (lib "eagle-import") (part "R-EU_R0805"))
    )
    (comp (ref "R44")
      (value "187")
      (footprint "eagle-import:R0805")
      (libsource (lib "eagle-import") (part "R-EU_R0805"))
    )
    (comp (ref "R45")
      (value "187")
      (footprint "eagle-import:R0805")
      (libsource (lib "eagle-import") (part "R-EU_R0805"))
    )
    (comp (ref "R46")
      (value "187")
      (footprint "eagle-import:R0805")
      (libsource (lib "eagle-import") (part "R-EU_R0805"))
    )
    (comp (ref "R47")
      (value "187")
      (footprint "eagle-import:R0805")
      (libsource (lib "eagle-import") (part "R-EU_R0805"))
    )
    (comp (ref "R48")
      (value "187")
      (footprint "eagle-import:R0805")
      (libsource (lib "eagle-import") (part "R-EU_R0805"))
    )
    (comp (ref "R49")
      (value "187")
      (footprint "eagle-import:R0805")
      (libsource (lib "eagle-import") (part "R-EU_R0805"))
    )
    (comp (ref "R50")
      (value "187")
      (footprint "eagle-import:R0805")
      (libsource (lib "eagle-import") (part "R-EU_R0805"))
    )
    (comp (ref "RESET")
      (value "RESET")
      (footprint "eagle-import:B3F-10XX")
      (fields (field (name "MPN") "B3F-1000"))
      (libsource (lib "eagle-import") (part "10-XX"))
    )
    (comp (ref "SHUTTER")
      (value "Red")
      (footprint "eagle-import:CHIP-LED0805")
      (libsource (lib "eagle-import") (part "LEDCHIP-LED0805"))
    )
    (comp (ref "STOP")
      (value "STOP")
      (footprint "eagle-import:B3F-10XX")
      (fields (field (name "MPN") "B3F-1000"))
      (libsource (lib "eagle-import") (part "10-XX"))
    )
    (comp (ref "U1")
      (value "VO1400AEFTR")
      (footprint "eagle-import:SOP4")
      (libsource (lib "eagle-import") (part "VO1400AEFTR"))
    )
    (comp (ref "U2")
      (value "VO1400AEFTR")
      (footprint "eagle-import:SOP4")
      (libsource (lib "eagle-import") (part "VO1400AEFTR"))
    )
    (comp (ref "U3")
      (value "VO1400AEFTR")
      (footprint "eagle-import:SOP4")
      (libsource (lib "eagle-import") (part "VO1400AEFTR"))
    )
    (comp (ref "U4")
      (value "VO1400AEFTR")
      (footprint "eagle-import:SOP4")
      (libsource (lib "eagle-import") (part "VO1400AEFTR"))
    )
    (comp (ref "U5")
      (value "VO1400AEFTR")
      (footprint "eagle-import:SOP4")
      (libsource (lib "eagle-import") (part "VO1400AEFTR"))
    )
    (comp (ref "U6")
      (value "VO1400AEFTR")
      (footprint "eagle-import:SOP4")
      (libsource (lib "eagle-import") (part "VO1400AEFTR"))
    )
    (comp (ref "U7")
      (value "VO1400AEFTR")
      (footprint "eagle-import:SOP4")
      (libsource (lib "eagle-import") (part "VO1400AEFTR"))
    )
    (comp (ref "U8")
      (value "VO1400AEFTR")
      (footprint "eagle-import:SOP4")
      (libsource (lib "eagle-import") (part "VO1400AEFTR"))
    )
    (comp (ref "UP")
      (value "UP")
      (footprint "eagle-import:B3F-10XX")
      (fields (field (name "MPN") "B3F-1000"))
      (libsource (lib "eagle-import") (part "10-XX"))
    )
  )
  (nets
    (net (code "1") (name "+5V") (class "Default")
      (node (ref "ICSP") (pin "2") (pinfunction "2_2") (pintype "passive"))
      (node (ref "ICSP1") (pin "2") (pinfunction "2_2") (pintype "passive"))
      (node (ref "JP3") (pin "2") (pinfunction "2_2") (pintype "passive"))
      (node (ref "LCD1") (pin "P$3") (pinfunction "VDD_P$3") (pintype "bidirectional"))
    )
    (net (code "2") (name "/A0") (class "Default")
      (node (ref "JP7") (pin "9") (pinfunction "9_9") (pintype "passive"))
      (node (ref "R1") (pin "2") (pinfunction "2_2") (pintype "passive"))
      (node (ref "R35") (pin "2") (pinfunction "2_2") (pintype "passive"))
    )
    (net (code "3") (name "/A1") (class "Default")
      (node (ref "JP7") (pin "8") (pinfunction "8_8") (pintype "passive"))
      (node (ref "R2") (pin "2") (pinfunction "2_2") (pintype "passive"))
      (node (ref "R36") (pin "2") (pinfunction "2_2") (pintype "passive"))
    )
    (net (code "4") (name "/A2") (class "Default")
      (node (ref "JP7") (pin "7") (pinfunction "7_7") (pintype "passive"))
      (node (ref "R3") (pin "2") (pinfunction "2_2") (pintype "passive"))
      (node (ref "R37") (pin "2") (pinfunction "2_2") (pintype "passive"))
    )
    (net (code "5") (name "/A3") (class "Default")
      (node (ref "JP7") (pin "6") (pinfunction "6_6") (pintype "passive"))
      (node (ref "R38") (pin "2") (pinfunction "2_2") (pintype "passive"))
      (node (ref "R4") (pin "2") (pinfunction "2_2") (pintype "passive"))
    )
    (net (code "6") (name "/A4") (class "Default")
      (node (ref "JP7") (pin "5") (pinfunction "5_5") (pintype "passive"))
      (node (ref "R39") (pin "2") (pinfunction "2_2") (pintype "passive"))
      (node (ref "R5") (pin "2") (pinfunction "2_2") (pintype "passive"))
    )
    (net (code "7") (name "/A5") (class "Default")
      (node (ref "JP7") (pin "4") (pinfunction "4_4") (pintype "passive"))
      (node (ref "R40") (pin "2") (pinfunction "2_2") (pintype "passive"))
      (node (ref "R6") (pin "2") (pinfunction "2_2") (pintype "passive"))
    )
    (net (code "8") (name "/A6") (class "Default")
      (node (ref "JP7") (pin "3") (pinfunction "3_3") (pintype "passive"))
      (node (ref "R41") (pin "2") (pinfunction "2_2") (pintype "passive"))
      (node (ref "R7") (pin "2") (pinfunction "2_2") (pintype "passive"))
    )
    (net (code "9") (name "/A7") (class "Default")
      (node (ref "JP7") (pin "2") (pinfunction "2_2") (pintype "passive"))
      (node (ref "R42") (pin "2") (pinfunction "2_2") (pintype "passive"))
      (node (ref "R8") (pin "2") (pinfunction "2_2") (pintype "passive"))
    )
    (net (code "10") (name "/B0") (class "Default")
      (node (ref "JP8") (pin "9") (pinfunction "9_9") (pintype "passive"))
      (node (ref "R9") (pin "2") (pinfunction "2_2") (pintype "passive"))
      (node (ref "U1") (pin "P$1") (pinfunction "A_P$1") (pintype "bidirectional"))
    )
    (net (code "11") (name "/B1") (class "Default")
      (node (ref "JP8") (pin "8") (pinfunction "8_8") (pintype "passive"))
      (node (ref "R10") (pin "2") (pinfunction "2_2") (pintype "passive"))
      (node (ref "U2") (pin "P$1") (pinfunction "A_P$1") (pintype "bidirectional"))
    )
    (net (code "12") (name "/B2") (class "Default")
      (node (ref "JP8") (pin "7") (pinfunction "7_7") (pintype "passive"))
      (node (ref "R11") (pin "2") (pinfunction "2_2") (pintype "passive"))
      (node (ref "U3") (pin "P$1") (pinfunction "A_P$1") (pintype "bidirectional"))
    )
    (net (code "13") (name "/B3") (class "Default")
      (node (ref "JP8") (pin "6") (pinfunction "6_6") (pintype "passive"))
      (node (ref "R12") (pin "2") (pinfunction "2_2") (pintype "passive"))
      (node (ref "U4") (pin "P$1") (pinfunction "A_P$1") (pintype "bidirectional"))
    )
    (net (code "14") (name "/B4") (class "Default")
      (node (ref "JP8") (pin "5") (pinfunction "5_5") (pintype "passive"))
      (node (ref "R13") (pin "2") (pinfunction "2_2") (pintype "passive"))
      (node (ref "U5") (pin "P$1") (pinfunction "A_P$1") (pintype "bidirectional"))
    )
    (net (code "15") (name "/B5") (class "Default")
      (node (ref "JP8") (pin "4") (pinfunction "4_4") (pintype "passive"))
      (node (ref "R14") (pin "2") (pinfunction "2_2") (pintype "passive"))
      (node (ref "U6") (pin "P$1") (pinfunction "A_P$1") (pintype "bidirectional"))
    )
    (net (code "16") (name "/B6") (class "Default")
      (node (ref "JP8") (pin "3") (pinfunction "3_3") (pintype "passive"))
      (node (ref "R15") (pin "2") (pinfunction "2_2") (pintype "passive"))
      (node (ref "U7") (pin "P$1") (pinfunction "A_P$1") (pintype "bidirectional"))
    )
    (net (code "17") (name "/B7") (class "Default")
      (node (ref "JP8") (pin "2") (pinfunction "2_2") (pintype "passive"))
      (node (ref "R16") (pin "2") (pinfunction "2_2") (pintype "passive"))
      (node (ref "U8") (pin "P$1") (pinfunction "A_P$1") (pintype "bidirectional"))
    )
    (net (code "18") (name "/C0") (class "Default")
      (node (ref "JP9") (pin "9") (pinfunction "9_9") (pintype "passive"))
      (node (ref "R17") (pin "2") (pinfunction "2_2") (pintype "passive"))
      (node (ref "R43") (pin "2") (pinfunction "2_2") (pintype "passive"))
    )
    (net (code "19") (name "/C1") (class "Default")
      (node (ref "JP9") (pin "8") (pinfunction "8_8") (pintype "passive"))
      (node (ref "R18") (pin "2") (pinfunction "2_2") (pintype "passive"))
      (node (ref "R44") (pin "2") (pinfunction "2_2") (pintype "passive"))
    )
    (net (code "20") (name "/C2") (class "Default")
      (node (ref "JP9") (pin "7") (pinfunction "7_7") (pintype "passive"))
      (node (ref "R19") (pin "2") (pinfunction "2_2") (pintype "passive"))
      (node (ref "R45") (pin "2") (pinfunction "2_2") (pintype "passive"))
    )
    (net (code "21") (name "/C3") (class "Default")
      (node (ref "JP9") (pin "6") (pinfunction "6_6") (pintype "passive"))
      (node (ref "R20") (pin "2") (pinfunction "2_2") (pintype "passive"))
      (node (ref "R46") (pin "2") (pinfunction "2_2") (pintype "passive"))
    )
    (net (code "22") (name "/C4") (class "Default")
      (node (ref "JP9") (pin "5") (pinfunction "5_5") (pintype "passive"))
      (node (ref "R21") (pin "2") (pinfunction "2_2") (pintype "passive"))
      (node (ref "R47") (pin "2") (pinfunction "2_2") (pintype "passive"))
    )
    (net (code "23") (name "/C5") (class "Default")
      (node (ref "JP9") (pin "4") (pinfunction "4_4") (pintype "passive"))
      (node (ref "R22") (pin "2") (pinfunction "2_2") (pintype "passive"))
      (node (ref "R48") (pin "2") (pinfunction "2_2") (pintype "passive"))
    )
    (net (code "24") (name "/C6") (class "Default")
      (node (ref "JP9") (pin "3") (pinfunction "3_3") (pintype "passive"))
      (node (ref "R23") (pin "2") (pinfunction "2_2") (pintype "passive"))
      (node (ref "R49") (pin "2") (pinfunction "2_2") (pintype "passive"))
    )
    (net (code "25") (name "/C7") (class "Default")
      (node (ref "JP9") (pin "2") (pinfunction "2_2") (pintype "passive"))
      (node (ref "R24") (pin "2") (pinfunction "2_2") (pintype "passive"))
      (node (ref "R50") (pin "2") (pinfunction "2_2") (pintype "passive"))
    )
    (net (code "26") (name "/G0") (class "Default")
      (node (ref "QA0") (pin "C") (pinfunction "C_C") (pintype "passive"))
      (node (ref "QA10") (pin "C") (pinfunction "C_C") (pintype "passive"))
      (node (ref "QA14") (pin "C") (pinfunction "C_C") (pintype "passive"))
      (node (ref "QA5") (pin "C") (pinfunction "C_C") (pintype "passive"))
      (node (ref "QB0") (pin "C") (pinfunction "C_C") (pintype "passive"))
      (node (ref "QB10") (pin "C") (pinfunction "C_C") (pintype "passive"))
      (node (ref "QB14") (pin "C") (pinfunction "C_C") (pintype "passive"))
      (node (ref "QB5") (pin "C") (pinfunction "C_C") (pintype "passive"))
      (node (ref "QC0") (pin "C") (pinfunction "C_C") (pintype "passive"))
      (node (ref "QC10") (pin "C") (pinfunction "C_C") (pintype "passive"))
      (node (ref "QC14") (pin "C") (pinfunction "C_C") (pintype "passive"))
      (node (ref "QC5") (pin "C") (pinfunction "C_C") (pintype "passive"))
      (node (ref "QD0") (pin "C") (pinfunction "C_C") (pintype "passive"))
      (node (ref "QD10") (pin "C") (pinfunction "C_C") (pintype "passive"))
      (node (ref "QD14") (pin "C") (pinfunction "C_C") (pintype "passive"))
      (node (ref "QD5") (pin "C") (pinfunction "C_C") (pintype "passive"))
      (node (ref "U1") (pin "P$4") (pinfunction "S1_P$4") (pintype "bidirectional"))
    )
    (net (code "27") (name "/G1") (class "Default")
      (node (ref "QA1") (pin "C") (pinfunction "C_C") (pintype "passive"))
      (node (ref "QA11") (pin "C") (pinfunction "C_C") (pintype "passive"))
      (node (ref "QA15") (pin "C") (pinfunction "C_C") (pintype "passive"))
      (node (ref "QA6") (pin "C") (pinfunction "C_C") (pintype "passive"))
      (node (ref "QB1") (pin "C") (pinfunction "C_C") (pintype "passive"))
      (node (ref "QB11") (pin "C") (pinfunction "C_C") (pintype "passive"))
      (node (ref "QB15") (pin "C") (pinfunction "C_C") (pintype "passive"))
      (node (ref "QB6") (pin "C") (pinfunction "C_C") (pintype "passive"))
      (node (ref "QC1") (pin "C") (pinfunction "C_C") (pintype "passive"))
      (node (ref "QC11") (pin "C") (pinfunction "C_C") (pintype "passive"))
      (node (ref "QC15") (pin "C") (pinfunction "C_C") (pintype "passive"))
      (node (ref "QC6") (pin "C") (pinfunction "C_C") (pintype "passive"))
      (node (ref "QD1") (pin "C") (pinfunction "C_C") (pintype "passive"))
      (node (ref "QD11") (pin "C") (pinfunction "C_C") (pintype "passive"))
      (node (ref "QD15") (pin "C") (pinfunction "C_C") (pintype "passive"))
      (node (ref "QD6") (pin "C") (pinfunction "C_C") (pintype "passive"))
      (node (ref "U2") (pin "P$4") (pinfunction "S1_P$4") (pintype "bidirectional"))
    )
    (net (code "28") (name "/G2") (class "Default")
      (node (ref "QA12") (pin "C") (pinfunction "C_C") (pintype "passive"))
      (node (ref "QA16") (pin "C") (pinfunction "C_C") (pintype "passive"))
      (node (ref "QA2") (pin "C") (pinfunction "C_C") (pintype "passive"))
      (node (ref "QA7") (pin "C") (pinfunction "C_C") (pintype "passive"))
      (node (ref "QB12") (pin "C") (pinfunction "C_C") (pintype "passive"))
      (node (ref "QB16") (pin "C") (pinfunction "C_C") (pintype "passive"))
      (node (ref "QB2") (pin "C") (pinfunction "C_C") (pintype "passive"))
      (node (ref "QB7") (pin "C") (pinfunction "C_C") (pintype "passive"))
      (node (ref "QC12") (pin "C") (pinfunction "C_C") (pintype "passive"))
      (node (ref "QC16") (pin "C") (pinfunction "C_C") (pintype "passive"))
      (node (ref "QC2") (pin "C") (pinfunction "C_C") (pintype "passive"))
      (node (ref "QC7") (pin "C") (pinfunction "C_C") (pintype "passive"))
      (node (ref "QD12") (pin "C") (pinfunction "C_C") (pintype "passive"))
      (node (ref "QD16") (pin "C") (pinfunction "C_C") (pintype "passive"))
      (node (ref "QD2") (pin "C") (pinfunction "C_C") (pintype "passive"))
      (node (ref "QD7") (pin "C") (pinfunction "C_C") (pintype "passive"))
      (node (ref "U3") (pin "P$4") (pinfunction "S1_P$4") (pintype "bidirectional"))
    )
    (net (code "29") (name "/G3") (class "Default")
      (node (ref "QA13") (pin "C") (pinfunction "C_C") (pintype "passive"))
      (node (ref "QA17") (pin "C") (pinfunction "C_C") (pintype "passive"))
      (node (ref "QA3") (pin "C") (pinfunction "C_C") (pintype "passive"))
      (node (ref "QA8") (pin "C") (pinfunction "C_C") (pintype "passive"))
      (node (ref "QB13") (pin "C") (pinfunction "C_C") (pintype "passive"))
      (node (ref "QB17") (pin "C") (pinfunction "C_C") (pintype "passive"))
      (node (ref "QB3") (pin "C") (pinfunction "C_C") (pintype "passive"))
      (node (ref "QB8") (pin "C") (pinfunction "C_C") (pintype "passive"))
      (node (ref "QC13") (pin "C") (pinfunction "C_C") (pintype "passive"))
      (node (ref "QC17") (pin "C") (pinfunction "C_C") (pintype "passive"))
      (node (ref "QC3") (pin "C") (pinfunction "C_C") (pintype "passive"))
      (node (ref "QC8") (pin "C") (pinfunction "C_C") (pintype "passive"))
      (node (ref "QD13") (pin "C") (pinfunction "C_C") (pintype "passive"))
      (node (ref "QD17") (pin "C") (pinfunction "C_C") (pintype "passive"))
      (node (ref "QD3") (pin "C") (pinfunction "C_C") (pintype "passive"))
      (node (ref "QD8") (pin "C") (pinfunction "C_C") (pintype "passive"))
      (node (ref "U4") (pin "P$4") (pinfunction "S1_P$4") (pintype "bidirectional"))
    )
    (net (code "30") (name "/G4") (class "Default")
      (node (ref "QA18") (pin "C") (pinfunction "C_C") (pintype "passive"))
      (node (ref "QA25") (pin "C") (pinfunction "C_C") (pintype "passive"))
      (node (ref "QA4") (pin "C") (pinfunction "C_C") (pintype "passive"))
      (node (ref "QA9") (pin "C") (pinfunction "C_C") (pintype "passive"))
      (node (ref "QB18") (pin "C") (pinfunction "C_C") (pintype "passive"))
      (node (ref "QB25") (pin "C") (pinfunction "C_C") (pintype "passive"))
      (node (ref "QB4") (pin "C") (pinfunction "C_C") (pintype "passive"))
      (node (ref "QB9") (pin "C") (pinfunction "C_C") (pintype "passive"))
      (node (ref "QC18") (pin "C") (pinfunction "C_C") (pintype "passive"))
      (node (ref "QC25") (pin "C") (pinfunction "C_C") (pintype "passive"))
      (node (ref "QC4") (pin "C") (pinfunction "C_C") (pintype "passive"))
      (node (ref "QC9") (pin "C") (pinfunction "C_C") (pintype "passive"))
      (node (ref "QD18") (pin "C") (pinfunction "C_C") (pintype "passive"))
      (node (ref "QD25") (pin "C") (pinfunction "C_C") (pintype "passive"))
      (node (ref "QD4") (pin "C") (pinfunction "C_C") (pintype "passive"))
      (node (ref "QD9") (pin "C") (pinfunction "C_C") (pintype "passive"))
      (node (ref "U5") (pin "P$4") (pinfunction "S1_P$4") (pintype "bidirectional"))
    )
    (net (code "31") (name "/G5") (class "Default")
      (node (ref "QA19") (pin "C") (pinfunction "C_C") (pintype "passive"))
      (node (ref "QA22") (pin "C") (pinfunction "C_C") (pintype "passive"))
      (node (ref "QA26") (pin "C") (pinfunction "C_C") (pintype "passive"))
      (node (ref "QA29") (pin "C") (pinfunction "C_C") (pintype "passive"))
      (node (ref "QB19") (pin "C") (pinfunction "C_C") (pintype "passive"))
      (node (ref "QB22") (pin "C") (pinfunction "C_C") (pintype "passive"))
      (node (ref "QB26") (pin "C") (pinfunction "C_C") (pintype "passive"))
      (node (ref "QB29") (pin "C") (pinfunction "C_C") (pintype "passive"))
      (node (ref "QC19") (pin "C") (pinfunction "C_C") (pintype "passive"))
      (node (ref "QC22") (pin "C") (pinfunction "C_C") (pintype "passive"))
      (node (ref "QC26") (pin "C") (pinfunction "C_C") (pintype "passive"))
      (node (ref "QC29") (pin "C") (pinfunction "C_C") (pintype "passive"))
      (node (ref "QD19") (pin "C") (pinfunction "C_C") (pintype "passive"))
      (node (ref "QD22") (pin "C") (pinfunction "C_C") (pintype "passive"))
      (node (ref "QD26") (pin "C") (pinfunction "C_C") (pintype "passive"))
      (node (ref "QD29") (pin "C") (pinfunction "C_C") (pintype "passive"))
      (node (ref "U6") (pin "P$4") (pinfunction "S1_P$4") (pintype "bidirectional"))
    )
    (net (code "32") (name "/G6") (class "Default")
      (node (ref "QA20") (pin "C") (pinfunction "C_C") (pintype "passive"))
      (node (ref "QA23") (pin "C") (pinfunction "C_C") (pintype "passive"))
      (node (ref "QA27") (pin "C") (pinfunction "C_C") (pintype "passive"))
      (node (ref "QA30") (pin "C") (pinfunction "C_C") (pintype "passive"))
      (node (ref "QB20") (pin "C") (pinfunction "C_C") (pintype "passive"))
      (node (ref "QB23") (pin "C") (pinfunction "C_C") (pintype "passive"))
      (node (ref "QB27") (pin "C") (pinfunction "C_C") (pintype "passive"))
      (node (ref "QB30") (pin "C") (pinfunction "C_C") (pintype "passive"))
      (node (ref "QC20") (pin "C") (pinfunction "C_C") (pintype "passive"))
      (node (ref "QC23") (pin "C") (pinfunction "C_C") (pintype "passive"))
      (node (ref "QC27") (pin "C") (pinfunction "C_C") (pintype "passive"))
      (node (ref "QC30") (pin "C") (pinfunction "C_C") (pintype "passive"))
      (node (ref "QD20") (pin "C") (pinfunction "C_C") (pintype "passive"))
      (node (ref "QD23") (pin "C") (pinfunction "C_C") (pintype "passive"))
      (node (ref "QD27") (pin "C") (pinfunction "C_C") (pintype "passive"))
      (node (ref "QD30") (pin "C") (pinfunction "C_C") (pintype "passive"))
      (node (ref "U7") (pin "P$4") (pinfunction "S1_P$4") (pintype "bidirectional"))
    )
    (net (code "33") (name "/G7") (class "Default")
      (node (ref "QA21") (pin "C") (pinfunction "C_C") (pintype "passive"))
      (node (ref "QA24") (pin "C") (pinfunction "C_C") (pintype "passive"))
      (node (ref "QA28") (pin "C") (pinfunction "C_C") (pintype "passive"))
      (node (ref "QA31") (pin "C") (pinfunction "C_C") (pintype "passive"))
      (node (ref "QB21") (pin "C") (pinfunction "C_C") (pintype "passive"))
      (node (ref "QB24") (pin "C") (pinfunction "C_C") (pintype "passive"))
      (node (ref "QB28") (pin "C") (pinfunction "C_C") (pintype "passive"))
      (node (ref "QB31") (pin "C") (pinfunction "C_C") (pintype "passive"))
      (node (ref "QC21") (pin "C") (pinfunction "C_C") (pintype "passive"))
      (node (ref "QC24") (pin "C") (pinfunction "C_C") (pintype "passive"))
      (node (ref "QC28") (pin "C") (pinfunction "C_C") (pintype "passive"))
      (node (ref "QC31") (pin "C") (pinfunction "C_C") (pintype "passive"))
      (node (ref "QD21") (pin "C") (pinfunction "C_C") (pintype "passive"))
      (node (ref "QD24") (pin "C") (pinfunction "C_C") (pintype "passive"))
      (node (ref "QD28") (pin "C") (pinfunction "C_C") (pintype "passive"))
      (node (ref "QD31") (pin "C") (pinfunction "C_C") (pintype "passive"))
      (node (ref "U8") (pin "P$4") (pinfunction "S1_P$4") (pintype "bidirectional"))
    )
    (net (code "34") (name "/PB1") (class "Default")
      (node (ref "ICSP") (pin "3") (pinfunction "3_3") (pintype "passive"))
      (node (ref "ICSP1") (pin "3") (pinfunction "3_3") (pintype "passive"))
    )
    (net (code "35") (name "/PB2") (class "Default")
      (node (ref "ICSP") (pin "4") (pinfunction "4_4") (pintype "passive"))
      (node (ref "ICSP1") (pin "4") (pinfunction "4_4") (pintype "passive"))
    )
    (net (code "36") (name "/PB3") (class "Default")
      (node (ref "ICSP") (pin "1") (pinfunction "1_1") (pintype "passive"))
      (node (ref "ICSP1") (pin "1") (pinfunction "1_1") (pintype "passive"))
    )
    (net (code "37") (name "/RESET") (class "Default")
      (node (ref "ICSP") (pin "5") (pinfunction "5_5") (pintype "passive"))
      (node (ref "ICSP1") (pin "5") (pinfunction "5_5") (pintype "passive"))
      (node (ref "RESET") (pin "1") (pinfunction "S_1") (pintype "passive"))
      (node (ref "RESET") (pin "2") (pinfunction "S1_2") (pintype "passive"))
    )
    (net (code "38") (name "/RXD2") (class "Default")
      (node (ref "JP3") (pin "6") (pinfunction "6_6") (pintype "passive"))
    )
    (net (code "39") (name "/SCL") (class "Default")
      (node (ref "JP3") (pin "1") (pinfunction "1_1") (pintype "passive"))
    )
    (net (code "40") (name "/SDA") (class "Default")
      (node (ref "JP3") (pin "3") (pinfunction "3_3") (pintype "passive"))
    )
    (net (code "41") (name "/SW1") (class "Default")
      (node (ref "JP3") (pin "7") (pinfunction "7_7") (pintype "passive"))
      (node (ref "STOP") (pin "1") (pinfunction "S_1") (pintype "passive"))
      (node (ref "STOP") (pin "2") (pinfunction "S1_2") (pintype "passive"))
    )
    (net (code "42") (name "/SW2") (class "Default")
      (node (ref "GO") (pin "1") (pinfunction "S_1") (pintype "passive"))
      (node (ref "GO") (pin "2") (pinfunction "S1_2") (pintype "passive"))
      (node (ref "JP3") (pin "9") (pinfunction "9_9") (pintype "passive"))
    )
    (net (code "43") (name "/SW3") (class "Default")
      (node (ref "JP3") (pin "11") (pinfunction "11_11") (pintype "passive"))
      (node (ref "UP") (pin "1") (pinfunction "S_1") (pintype "passive"))
      (node (ref "UP") (pin "2") (pinfunction "S1_2") (pintype "passive"))
    )
    (net (code "44") (name "/SW4") (class "Default")
      (node (ref "DOWN") (pin "1") (pinfunction "S_1") (pintype "passive"))
      (node (ref "DOWN") (pin "2") (pinfunction "S1_2") (pintype "passive"))
      (node (ref "JP3") (pin "13") (pinfunction "13_13") (pintype "passive"))
    )
    (net (code "45") (name "/SW5") (class "Default")
      (node (ref "FOCUSON") (pin "1") (pinfunction "S_1") (pintype "passive"))
      (node (ref "FOCUSON") (pin "2") (pinfunction "S1_2") (pintype "passive"))
      (node (ref "JP3") (pin "15") (pinfunction "15_15") (pintype "passive"))
    )
    (net (code "46") (name "/TXD2") (class "Default")
      (node (ref "JP3") (pin "5") (pinfunction "5_5") (pintype "passive"))
      (node (ref "LCD1") (pin "P$1") (pinfunction "RX_P$1") (pintype "bidirectional"))
    )
    (net (code "47") (name "GND") (class "Default")
      (node (ref "A0") (pin "C") (pinfunction "C_C") (pintype "passive"))
      (node (ref "A1") (pin "C") (pinfunction "C_C") (pintype "passive"))
      (node (ref "A2") (pin "C") (pinfunction "C_C") (pintype "passive"))
      (node (ref "A3") (pin "C") (pinfunction "C_C") (pintype "passive"))
      (node (ref "A4") (pin "C") (pinfunction "C_C") (pintype "passive"))
      (node (ref "A5") (pin "C") (pinfunction "C_C") (pintype "passive"))
      (node (ref "A6") (pin "C") (pinfunction "C_C") (pintype "passive"))
      (node (ref "A7") (pin "C") (pinfunction "C_C") (pintype "passive"))
      (node (ref "B0") (pin "C") (pinfunction "C_C") (pintype "passive"))
      (node (ref "B1") (pin "C") (pinfunction "C_C") (pintype "passive"))
      (node (ref "B2") (pin "C") (pinfunction "C_C") (pintype "passive"))
      (node (ref "B3") (pin "C") (pinfunction "C_C") (pintype "passive"))
      (node (ref "B4") (pin "C") (pinfunction "C_C") (pintype "passive"))
      (node (ref "B5") (pin "C") (pinfunction "C_C") (pintype "passive"))
      (node (ref "B6") (pin "C") (pinfunction "C_C") (pintype "passive"))
      (node (ref "B7") (pin "C") (pinfunction "C_C") (pintype "passive"))
      (node (ref "C0") (pin "C") (pinfunction "C_C") (pintype "passive"))
      (node (ref "C1") (pin "C") (pinfunction "C_C") (pintype "passive"))
      (node (ref "C2") (pin "C") (pinfunction "C_C") (pintype "passive"))
      (node (ref "C3") (pin "C") (pinfunction "C_C") (pintype "passive"))
      (node (ref "C4") (pin "C") (pinfunction "C_C") (pintype "passive"))
      (node (ref "C5") (pin "C") (pinfunction "C_C") (pintype "passive"))
      (node (ref "C6") (pin "C") (pinfunction "C_C") (pintype "passive"))
      (node (ref "C7") (pin "C") (pinfunction "C_C") (pintype "passive"))
      (node (ref "DOWN") (pin "3") (pinfunction "P_3") (pintype "passive"))
      (node (ref "DOWN") (pin "4") (pinfunction "P1_4") (pintype "passive"))
      (node (ref "FOCUS") (pin "C") (pinfunction "C_C") (pintype "passive"))
      (node (ref "FOCUSON") (pin "3") (pinfunction "P_3") (pintype "passive"))
      (node (ref "FOCUSON") (pin "4") (pinfunction "P1_4") (pintype "passive"))
      (node (ref "GO") (pin "3") (pinfunction "P_3") (pintype "passive"))
      (node (ref "GO") (pin "4") (pinfunction "P1_4") (pintype "passive"))
      (node (ref "ICSP") (pin "6") (pinfunction "6_6") (pintype "passive"))
      (node (ref "ICSP1") (pin "6") (pinfunction "6_6") (pintype "passive"))
      (node (ref "JP3") (pin "10") (pinfunction "10_10") (pintype "passive"))
      (node (ref "JP3") (pin "12") (pinfunction "12_12") (pintype "passive"))
      (node (ref "JP3") (pin "14") (pinfunction "14_14") (pintype "passive"))
      (node (ref "JP3") (pin "16") (pinfunction "16_16") (pintype "passive"))
      (node (ref "JP3") (pin "4") (pinfunction "4_4") (pintype "passive"))
      (node (ref "JP3") (pin "8") (pinfunction "8_8") (pintype "passive"))
      (node (ref "JP7") (pin "10") (pinfunction "10_10") (pintype "passive"))
      (node (ref "JP8") (pin "10") (pinfunction "10_10") (pintype "passive"))
      (node (ref "JP9") (pin "10") (pinfunction "10_10") (pintype "passive"))
      (node (ref "LCD1") (pin "P$2") (pinfunction "GND_P$2") (pintype "bidirectional"))
      (node (ref "R27") (pin "1") (pinfunction "1_1") (pintype "passive"))
      (node (ref "R28") (pin "1") (pinfunction "1_1") (pintype "passive"))
      (node (ref "R29") (pin "1") (pinfunction "1_1") (pintype "passive"))
      (node (ref "R30") (pin "1") (pinfunction "1_1") (pintype "passive"))
      (node (ref "R31") (pin "1") (pinfunction "1_1") (pintype "passive"))
      (node (ref "R32") (pin "1") (pinfunction "1_1") (pintype "passive"))
      (node (ref "R33") (pin "1") (pinfunction "1_1") (pintype "passive"))
      (node (ref "R34") (pin "1") (pinfunction "1_1") (pintype "passive"))
      (node (ref "RESET") (pin "3") (pinfunction "P_3") (pintype "passive"))
      (node (ref "RESET") (pin "4") (pinfunction "P1_4") (pintype "passive"))
      (node (ref "SHUTTER") (pin "C") (pinfunction "C_C") (pintype "passive"))
      (node (ref "STOP") (pin "3") (pinfunction "P_3") (pintype "passive"))
      (node (ref "STOP") (pin "4") (pinfunction "P1_4") (pintype "passive"))
      (node (ref "U1") (pin "P$3") (pinfunction "S2_P$3") (pintype "bidirectional"))
      (node (ref "U2") (pin "P$3") (pinfunction "S2_P$3") (pintype "bidirectional"))
      (node (ref "U3") (pin "P$3") (pinfunction "S2_P$3") (pintype "bidirectional"))
      (node (ref "U4") (pin "P$3") (pinfunction "S2_P$3") (pintype "bidirectional"))
      (node (ref "U5") (pin "P$3") (pinfunction "S2_P$3") (pintype "bidirectional"))
      (node (ref "U6") (pin "P$3") (pinfunction "S2_P$3") (pintype "bidirectional"))
      (node (ref "U7") (pin "P$3") (pinfunction "S2_P$3") (pintype "bidirectional"))
      (node (ref "U8") (pin "P$3") (pinfunction "S2_P$3") (pintype "bidirectional"))
      (node (ref "UP") (pin "3") (pinfunction "P_3") (pintype "passive"))
      (node (ref "UP") (pin "4") (pinfunction "P1_4") (pintype "passive"))
    )
    (net (code "48") (name "Net-(A0-PadA)") (class "Default")
      (node (ref "A0") (pin "A") (pinfunction "A_A") (pintype "passive"))
      (node (ref "R1") (pin "1") (pinfunction "1_1") (pintype "passive"))
    )
    (net (code "49") (name "Net-(A1-PadA)") (class "Default")
      (node (ref "A1") (pin "A") (pinfunction "A_A") (pintype "passive"))
      (node (ref "R2") (pin "1") (pinfunction "1_1") (pintype "passive"))
    )
    (net (code "50") (name "Net-(A2-PadA)") (class "Default")
      (node (ref "A2") (pin "A") (pinfunction "A_A") (pintype "passive"))
      (node (ref "R3") (pin "1") (pinfunction "1_1") (pintype "passive"))
    )
    (net (code "51") (name "Net-(A3-PadA)") (class "Default")
      (node (ref "A3") (pin "A") (pinfunction "A_A") (pintype "passive"))
      (node (ref "R4") (pin "1") (pinfunction "1_1") (pintype "passive"))
    )
    (net (code "52") (name "Net-(A4-PadA)") (class "Default")
      (node (ref "A4") (pin "A") (pinfunction "A_A") (pintype "passive"))
      (node (ref "R5") (pin "1") (pinfunction "1_1") (pintype "passive"))
    )
    (net (code "53") (name "Net-(A5-PadA)") (class "Default")
      (node (ref "A5") (pin "A") (pinfunction "A_A") (pintype "passive"))
      (node (ref "R6") (pin "1") (pinfunction "1_1") (pintype "passive"))
    )
    (net (code "54") (name "Net-(A6-PadA)") (class "Default")
      (node (ref "A6") (pin "A") (pinfunction "A_A") (pintype "passive"))
      (node (ref "R7") (pin "1") (pinfunction "1_1") (pintype "passive"))
    )
    (net (code "55") (name "Net-(A7-PadA)") (class "Default")
      (node (ref "A7") (pin "A") (pinfunction "A_A") (pintype "passive"))
      (node (ref "R8") (pin "1") (pinfunction "1_1") (pintype "passive"))
    )
    (net (code "56") (name "Net-(B0-PadA)") (class "Default")
      (node (ref "B0") (pin "A") (pinfunction "A_A") (pintype "passive"))
      (node (ref "R9") (pin "1") (pinfunction "1_1") (pintype "passive"))
    )
    (net (code "57") (name "Net-(B1-PadA)") (class "Default")
      (node (ref "B1") (pin "A") (pinfunction "A_A") (pintype "passive"))
      (node (ref "R10") (pin "1") (pinfunction "1_1") (pintype "passive"))
    )
    (net (code "58") (name "Net-(B2-PadA)") (class "Default")
      (node (ref "B2") (pin "A") (pinfunction "A_A") (pintype "passive"))
      (node (ref "R11") (pin "1") (pinfunction "1_1") (pintype "passive"))
    )
    (net (code "59") (name "Net-(B3-PadA)") (class "Default")
      (node (ref "B3") (pin "A") (pinfunction "A_A") (pintype "passive"))
      (node (ref "R12") (pin "1") (pinfunction "1_1") (pintype "passive"))
    )
    (net (code "60") (name "Net-(B4-PadA)") (class "Default")
      (node (ref "B4") (pin "A") (pinfunction "A_A") (pintype "passive"))
      (node (ref "R13") (pin "1") (pinfunction "1_1") (pintype "passive"))
    )
    (net (code "61") (name "Net-(B5-PadA)") (class "Default")
      (node (ref "B5") (pin "A") (pinfunction "A_A") (pintype "passive"))
      (node (ref "R14") (pin "1") (pinfunction "1_1") (pintype "passive"))
    )
    (net (code "62") (name "Net-(B6-PadA)") (class "Default")
      (node (ref "B6") (pin "A") (pinfunction "A_A") (pintype "passive"))
      (node (ref "R15") (pin "1") (pinfunction "1_1") (pintype "passive"))
    )
    (net (code "63") (name "Net-(B7-PadA)") (class "Default")
      (node (ref "B7") (pin "A") (pinfunction "A_A") (pintype "passive"))
      (node (ref "R16") (pin "1") (pinfunction "1_1") (pintype "passive"))
    )
    (net (code "64") (name "Net-(C0-PadA)") (class "Default")
      (node (ref "C0") (pin "A") (pinfunction "A_A") (pintype "passive"))
      (node (ref "R17") (pin "1") (pinfunction "1_1") (pintype "passive"))
    )
    (net (code "65") (name "Net-(C1-PadA)") (class "Default")
      (node (ref "C1") (pin "A") (pinfunction "A_A") (pintype "passive"))
      (node (ref "R18") (pin "1") (pinfunction "1_1") (pintype "passive"))
    )
    (net (code "66") (name "Net-(C2-PadA)") (class "Default")
      (node (ref "C2") (pin "A") (pinfunction "A_A") (pintype "passive"))
      (node (ref "R19") (pin "1") (pinfunction "1_1") (pintype "passive"))
    )
    (net (code "67") (name "Net-(C3-PadA)") (class "Default")
      (node (ref "C3") (pin "A") (pinfunction "A_A") (pintype "passive"))
      (node (ref "R20") (pin "1") (pinfunction "1_1") (pintype "passive"))
    )
    (net (code "68") (name "Net-(C4-PadA)") (class "Default")
      (node (ref "C4") (pin "A") (pinfunction "A_A") (pintype "passive"))
      (node (ref "R21") (pin "1") (pinfunction "1_1") (pintype "passive"))
    )
    (net (code "69") (name "Net-(C5-PadA)") (class "Default")
      (node (ref "C5") (pin "A") (pinfunction "A_A") (pintype "passive"))
      (node (ref "R22") (pin "1") (pinfunction "1_1") (pintype "passive"))
    )
    (net (code "70") (name "Net-(C6-PadA)") (class "Default")
      (node (ref "C6") (pin "A") (pinfunction "A_A") (pintype "passive"))
      (node (ref "R23") (pin "1") (pinfunction "1_1") (pintype "passive"))
    )
    (net (code "71") (name "Net-(C7-PadA)") (class "Default")
      (node (ref "C7") (pin "A") (pinfunction "A_A") (pintype "passive"))
      (node (ref "R24") (pin "1") (pinfunction "1_1") (pintype "passive"))
    )
    (net (code "72") (name "Net-(FOCUS-PadA)") (class "Default")
      (node (ref "FOCUS") (pin "A") (pinfunction "A_A") (pintype "passive"))
      (node (ref "R25") (pin "1") (pinfunction "1_1") (pintype "passive"))
    )
    (net (code "73") (name "Net-(JP4-Pad1)") (class "Default")
      (node (ref "JP4") (pin "1") (pinfunction "1_1") (pintype "passive"))
      (node (ref "R25") (pin "2") (pinfunction "2_2") (pintype "passive"))
    )
    (net (code "74") (name "Net-(JP4-Pad2)") (class "Default")
      (node (ref "JP4") (pin "2") (pinfunction "2_2") (pintype "passive"))
      (node (ref "R26") (pin "2") (pinfunction "2_2") (pintype "passive"))
    )
    (net (code "75") (name "Net-(QA0-PadA)") (class "Default")
      (node (ref "QA0") (pin "A") (pinfunction "A_A") (pintype "passive"))
      (node (ref "QA1") (pin "A") (pinfunction "A_A") (pintype "passive"))
      (node (ref "QA19") (pin "A") (pinfunction "A_A") (pintype "passive"))
      (node (ref "QA2") (pin "A") (pinfunction "A_A") (pintype "passive"))
      (node (ref "QA20") (pin "A") (pinfunction "A_A") (pintype "passive"))
      (node (ref "QA21") (pin "A") (pinfunction "A_A") (pintype "passive"))
      (node (ref "QA3") (pin "A") (pinfunction "A_A") (pintype "passive"))
      (node (ref "QA4") (pin "A") (pinfunction "A_A") (pintype "passive"))
      (node (ref "R35") (pin "1") (pinfunction "1_1") (pintype "passive"))
    )
    (net (code "76") (name "Net-(QA10-PadA)") (class "Default")
      (node (ref "QA10") (pin "A") (pinfunction "A_A") (pintype "passive"))
      (node (ref "QA11") (pin "A") (pinfunction "A_A") (pintype "passive"))
      (node (ref "QA12") (pin "A") (pinfunction "A_A") (pintype "passive"))
      (node (ref "QA13") (pin "A") (pinfunction "A_A") (pintype "passive"))
      (node (ref "QA25") (pin "A") (pinfunction "A_A") (pintype "passive"))
      (node (ref "QA26") (pin "A") (pinfunction "A_A") (pintype "passive"))
      (node (ref "QA27") (pin "A") (pinfunction "A_A") (pintype "passive"))
      (node (ref "QA28") (pin "A") (pinfunction "A_A") (pintype "passive"))
      (node (ref "R37") (pin "1") (pinfunction "1_1") (pintype "passive"))
    )
    (net (code "77") (name "Net-(QA14-PadA)") (class "Default")
      (node (ref "QA14") (pin "A") (pinfunction "A_A") (pintype "passive"))
      (node (ref "QA15") (pin "A") (pinfunction "A_A") (pintype "passive"))
      (node (ref "QA16") (pin "A") (pinfunction "A_A") (pintype "passive"))
      (node (ref "QA17") (pin "A") (pinfunction "A_A") (pintype "passive"))
      (node (ref "QA18") (pin "A") (pinfunction "A_A") (pintype "passive"))
      (node (ref "QA29") (pin "A") (pinfunction "A_A") (pintype "passive"))
      (node (ref "QA30") (pin "A") (pinfunction "A_A") (pintype "passive"))
      (node (ref "QA31") (pin "A") (pinfunction "A_A") (pintype "passive"))
      (node (ref "R38") (pin "1") (pinfunction "1_1") (pintype "passive"))
    )
    (net (code "78") (name "Net-(QA22-PadA)") (class "Default")
      (node (ref "QA22") (pin "A") (pinfunction "A_A") (pintype "passive"))
      (node (ref "QA23") (pin "A") (pinfunction "A_A") (pintype "passive"))
      (node (ref "QA24") (pin "A") (pinfunction "A_A") (pintype "passive"))
      (node (ref "QA5") (pin "A") (pinfunction "A_A") (pintype "passive"))
      (node (ref "QA6") (pin "A") (pinfunction "A_A") (pintype "passive"))
      (node (ref "QA7") (pin "A") (pinfunction "A_A") (pintype "passive"))
      (node (ref "QA8") (pin "A") (pinfunction "A_A") (pintype "passive"))
      (node (ref "QA9") (pin "A") (pinfunction "A_A") (pintype "passive"))
      (node (ref "R36") (pin "1") (pinfunction "1_1") (pintype "passive"))
    )
    (net (code "79") (name "Net-(QB0-PadA)") (class "Default")
      (node (ref "QB0") (pin "A") (pinfunction "A_A") (pintype "passive"))
      (node (ref "QB1") (pin "A") (pinfunction "A_A") (pintype "passive"))
      (node (ref "QB19") (pin "A") (pinfunction "A_A") (pintype "passive"))
      (node (ref "QB2") (pin "A") (pinfunction "A_A") (pintype "passive"))
      (node (ref "QB20") (pin "A") (pinfunction "A_A") (pintype "passive"))
      (node (ref "QB21") (pin "A") (pinfunction "A_A") (pintype "passive"))
      (node (ref "QB3") (pin "A") (pinfunction "A_A") (pintype "passive"))
      (node (ref "QB4") (pin "A") (pinfunction "A_A") (pintype "passive"))
      (node (ref "R39") (pin "1") (pinfunction "1_1") (pintype "passive"))
    )
    (net (code "80") (name "Net-(QB10-PadA)") (class "Default")
      (node (ref "QB10") (pin "A") (pinfunction "A_A") (pintype "passive"))
      (node (ref "QB11") (pin "A") (pinfunction "A_A") (pintype "passive"))
      (node (ref "QB12") (pin "A") (pinfunction "A_A") (pintype "passive"))
      (node (ref "QB13") (pin "A") (pinfunction "A_A") (pintype "passive"))
      (node (ref "QB25") (pin "A") (pinfunction "A_A") (pintype "passive"))
      (node (ref "QB26") (pin "A") (pinfunction "A_A") (pintype "passive"))
      (node (ref "QB27") (pin "A") (pinfunction "A_A") (pintype "passive"))
      (node (ref "QB28") (pin "A") (pinfunction "A_A") (pintype "passive"))
      (node (ref "R41") (pin "1") (pinfunction "1_1") (pintype "passive"))
    )
    (net (code "81") (name "Net-(QB14-PadA)") (class "Default")
      (node (ref "QB14") (pin "A") (pinfunction "A_A") (pintype "passive"))
      (node (ref "QB15") (pin "A") (pinfunction "A_A") (pintype "passive"))
      (node (ref "QB16") (pin "A") (pinfunction "A_A") (pintype "passive"))
      (node (ref "QB17") (pin "A") (pinfunction "A_A") (pintype "passive"))
      (node (ref "QB18") (pin "A") (pinfunction "A_A") (pintype "passive"))
      (node (ref "QB29") (pin "A") (pinfunction "A_A") (pintype "passive"))
      (node (ref "QB30") (pin "A") (pinfunction "A_A") (pintype "passive"))
      (node (ref "QB31") (pin "A") (pinfunction "A_A") (pintype "passive"))
      (node (ref "R42") (pin "1") (pinfunction "1_1") (pintype "passive"))
    )
    (net (code "82") (name "Net-(QB22-PadA)") (class "Default")
      (node (ref "QB22") (pin "A") (pinfunction "A_A") (pintype "passive"))
      (node (ref "QB23") (pin "A") (pinfunction "A_A") (pintype "passive"))
      (node (ref "QB24") (pin "A") (pinfunction "A_A") (pintype "passive"))
      (node (ref "QB5") (pin "A") (pinfunction "A_A") (pintype "passive"))
      (node (ref "QB6") (pin "A") (pinfunction "A_A") (pintype "passive"))
      (node (ref "QB7") (pin "A") (pinfunction "A_A") (pintype "passive"))
      (node (ref "QB8") (pin "A") (pinfunction "A_A") (pintype "passive"))
      (node (ref "QB9") (pin "A") (pinfunction "A_A") (pintype "passive"))
      (node (ref "R40") (pin "1") (pinfunction "1_1") (pintype "passive"))
    )
    (net (code "83") (name "Net-(QC0-PadA)") (class "Default")
      (node (ref "QC0") (pin "A") (pinfunction "A_A") (pintype "passive"))
      (node (ref "QC1") (pin "A") (pinfunction "A_A") (pintype "passive"))
      (node (ref "QC19") (pin "A") (pinfunction "A_A") (pintype "passive"))
      (node (ref "QC2") (pin "A") (pinfunction "A_A") (pintype "passive"))
      (node (ref "QC20") (pin "A") (pinfunction "A_A") (pintype "passive"))
      (node (ref "QC21") (pin "A") (pinfunction "A_A") (pintype "passive"))
      (node (ref "QC3") (pin "A") (pinfunction "A_A") (pintype "passive"))
      (node (ref "QC4") (pin "A") (pinfunction "A_A") (pintype "passive"))
      (node (ref "R43") (pin "1") (pinfunction "1_1") (pintype "passive"))
    )
    (net (code "84") (name "Net-(QC10-PadA)") (class "Default")
      (node (ref "QC10") (pin "A") (pinfunction "A_A") (pintype "passive"))
      (node (ref "QC11") (pin "A") (pinfunction "A_A") (pintype "passive"))
      (node (ref "QC12") (pin "A") (pinfunction "A_A") (pintype "passive"))
      (node (ref "QC13") (pin "A") (pinfunction "A_A") (pintype "passive"))
      (node (ref "QC25") (pin "A") (pinfunction "A_A") (pintype "passive"))
      (node (ref "QC26") (pin "A") (pinfunction "A_A") (pintype "passive"))
      (node (ref "QC27") (pin "A") (pinfunction "A_A") (pintype "passive"))
      (node (ref "QC28") (pin "A") (pinfunction "A_A") (pintype "passive"))
      (node (ref "R45") (pin "1") (pinfunction "1_1") (pintype "passive"))
    )
    (net (code "85") (name "Net-(QC14-PadA)") (class "Default")
      (node (ref "QC14") (pin "A") (pinfunction "A_A") (pintype "passive"))
      (node (ref "QC15") (pin "A") (pinfunction "A_A") (pintype "passive"))
      (node (ref "QC16") (pin "A") (pinfunction "A_A") (pintype "passive"))
      (node (ref "QC17") (pin "A") (pinfunction "A_A") (pintype "passive"))
      (node (ref "QC18") (pin "A") (pinfunction "A_A") (pintype "passive"))
      (node (ref "QC29") (pin "A") (pinfunction "A_A") (pintype "passive"))
      (node (ref "QC30") (pin "A") (pinfunction "A_A") (pintype "passive"))
      (node (ref "QC31") (pin "A") (pinfunction "A_A") (pintype "passive"))
      (node (ref "R46") (pin "1") (pinfunction "1_1") (pintype "passive"))
    )
    (net (code "86") (name "Net-(QC22-PadA)") (class "Default")
      (node (ref "QC22") (pin "A") (pinfunction "A_A") (pintype "passive"))
      (node (ref "QC23") (pin "A") (pinfunction "A_A") (pintype "passive"))
      (node (ref "QC24") (pin "A") (pinfunction "A_A") (pintype "passive"))
      (node (ref "QC5") (pin "A") (pinfunction "A_A") (pintype "passive"))
      (node (ref "QC6") (pin "A") (pinfunction "A_A") (pintype "passive"))
      (node (ref "QC7") (pin "A") (pinfunction "A_A") (pintype "passive"))
      (node (ref "QC8") (pin "A") (pinfunction "A_A") (pintype "passive"))
      (node (ref "QC9") (pin "A") (pinfunction "A_A") (pintype "passive"))
      (node (ref "R44") (pin "1") (pinfunction "1_1") (pintype "passive"))
    )
    (net (code "87") (name "Net-(QD0-PadA)") (class "Default")
      (node (ref "QD0") (pin "A") (pinfunction "A_A") (pintype "passive"))
      (node (ref "QD1") (pin "A") (pinfunction "A_A") (pintype "passive"))
      (node (ref "QD19") (pin "A") (pinfunction "A_A") (pintype "passive"))
      (node (ref "QD2") (pin "A") (pinfunction "A_A") (pintype "passive"))
      (node (ref "QD20") (pin "A") (pinfunction "A_A") (pintype "passive"))
      (node (ref "QD21") (pin "A") (pinfunction "A_A") (pintype "passive"))
      (node (ref "QD3") (pin "A") (pinfunction "A_A") (pintype "passive"))
      (node (ref "QD4") (pin "A") (pinfunction "A_A") (pintype "passive"))
      (node (ref "R47") (pin "1") (pinfunction "1_1") (pintype "passive"))
    )
    (net (code "88") (name "Net-(QD10-PadA)") (class "Default")
      (node (ref "QD10") (pin "A") (pinfunction "A_A") (pintype "passive"))
      (node (ref "QD11") (pin "A") (pinfunction "A_A") (pintype "passive"))
      (node (ref "QD12") (pin "A") (pinfunction "A_A") (pintype "passive"))
      (node (ref "QD13") (pin "A") (pinfunction "A_A") (pintype "passive"))
      (node (ref "QD25") (pin "A") (pinfunction "A_A") (pintype "passive"))
      (node (ref "QD26") (pin "A") (pinfunction "A_A") (pintype "passive"))
      (node (ref "QD27") (pin "A") (pinfunction "A_A") (pintype "passive"))
      (node (ref "QD28") (pin "A") (pinfunction "A_A") (pintype "passive"))
      (node (ref "R49") (pin "1") (pinfunction "1_1") (pintype "passive"))
    )
    (net (code "89") (name "Net-(QD14-PadA)") (class "Default")
      (node (ref "QD14") (pin "A") (pinfunction "A_A") (pintype "passive"))
      (node (ref "QD15") (pin "A") (pinfunction "A_A") (pintype "passive"))
      (node (ref "QD16") (pin "A") (pinfunction "A_A") (pintype "passive"))
      (node (ref "QD17") (pin "A") (pinfunction "A_A") (pintype "passive"))
      (node (ref "QD18") (pin "A") (pinfunction "A_A") (pintype "passive"))
      (node (ref "QD29") (pin "A") (pinfunction "A_A") (pintype "passive"))
      (node (ref "QD30") (pin "A") (pinfunction "A_A") (pintype "passive"))
      (node (ref "QD31") (pin "A") (pinfunction "A_A") (pintype "passive"))
      (node (ref "R50") (pin "1") (pinfunction "1_1") (pintype "passive"))
    )
    (net (code "90") (name "Net-(QD22-PadA)") (class "Default")
      (node (ref "QD22") (pin "A") (pinfunction "A_A") (pintype "passive"))
      (node (ref "QD23") (pin "A") (pinfunction "A_A") (pintype "passive"))
      (node (ref "QD24") (pin "A") (pinfunction "A_A") (pintype "passive"))
      (node (ref "QD5") (pin "A") (pinfunction "A_A") (pintype "passive"))
      (node (ref "QD6") (pin "A") (pinfunction "A_A") (pintype "passive"))
      (node (ref "QD7") (pin "A") (pinfunction "A_A") (pintype "passive"))
      (node (ref "QD8") (pin "A") (pinfunction "A_A") (pintype "passive"))
      (node (ref "QD9") (pin "A") (pinfunction "A_A") (pintype "passive"))
      (node (ref "R48") (pin "1") (pinfunction "1_1") (pintype "passive"))
    )
    (net (code "91") (name "Net-(R26-Pad1)") (class "Default")
      (node (ref "R26") (pin "1") (pinfunction "1_1") (pintype "passive"))
      (node (ref "SHUTTER") (pin "A") (pinfunction "A_A") (pintype "passive"))
    )
    (net (code "92") (name "Net-(U1-K)") (class "Default")
      (node (ref "R27") (pin "2") (pinfunction "2_2") (pintype "passive"))
      (node (ref "U1") (pin "P$2") (pinfunction "K_P$2") (pintype "bidirectional"))
    )
    (net (code "93") (name "Net-(U2-K)") (class "Default")
      (node (ref "R28") (pin "2") (pinfunction "2_2") (pintype "passive"))
      (node (ref "U2") (pin "P$2") (pinfunction "K_P$2") (pintype "bidirectional"))
    )
    (net (code "94") (name "Net-(U3-K)") (class "Default")
      (node (ref "R29") (pin "2") (pinfunction "2_2") (pintype "passive"))
      (node (ref "U3") (pin "P$2") (pinfunction "K_P$2") (pintype "bidirectional"))
    )
    (net (code "95") (name "Net-(U4-K)") (class "Default")
      (node (ref "R30") (pin "2") (pinfunction "2_2") (pintype "passive"))
      (node (ref "U4") (pin "P$2") (pinfunction "K_P$2") (pintype "bidirectional"))
    )
    (net (code "96") (name "Net-(U5-K)") (class "Default")
      (node (ref "R31") (pin "2") (pinfunction "2_2") (pintype "passive"))
      (node (ref "U5") (pin "P$2") (pinfunction "K_P$2") (pintype "bidirectional"))
    )
    (net (code "97") (name "Net-(U6-K)") (class "Default")
      (node (ref "R32") (pin "2") (pinfunction "2_2") (pintype "passive"))
      (node (ref "U6") (pin "P$2") (pinfunction "K_P$2") (pintype "bidirectional"))
    )
    (net (code "98") (name "Net-(U7-K)") (class "Default")
      (node (ref "R33") (pin "2") (pinfunction "2_2") (pintype "passive"))
      (node (ref "U7") (pin "P$2") (pinfunction "K_P$2") (pintype "bidirectional"))
    )
    (net (code "99") (name "Net-(U8-K)") (class "Default")
      (node (ref "R34") (pin "2") (pinfunction "2_2") (pintype "passive"))
      (node (ref "U8") (pin "P$2") (pinfunction "K_P$2") (pintype "bidirectional"))
    )
    (net (code "100") (name "unconnected-(JP7-Pad1)") (class "Default")
      (node (ref "JP7") (pin "1") (pinfunction "1_1") (pintype "passive"))
    )
    (net (code "101") (name "unconnected-(JP8-Pad1)") (class "Default")
      (node (ref "JP8") (pin "1") (pinfunction "1_1") (pintype "passive"))
    )
    (net (code "102") (name "unconnected-(JP9-Pad1)") (class "Default")
      (node (ref "JP9") (pin "1") (pinfunction "1_1") (pintype "passive"))
    )
  )
)
